# mainboard.net
KiCad netlist of a schematic drawn in EAGLE
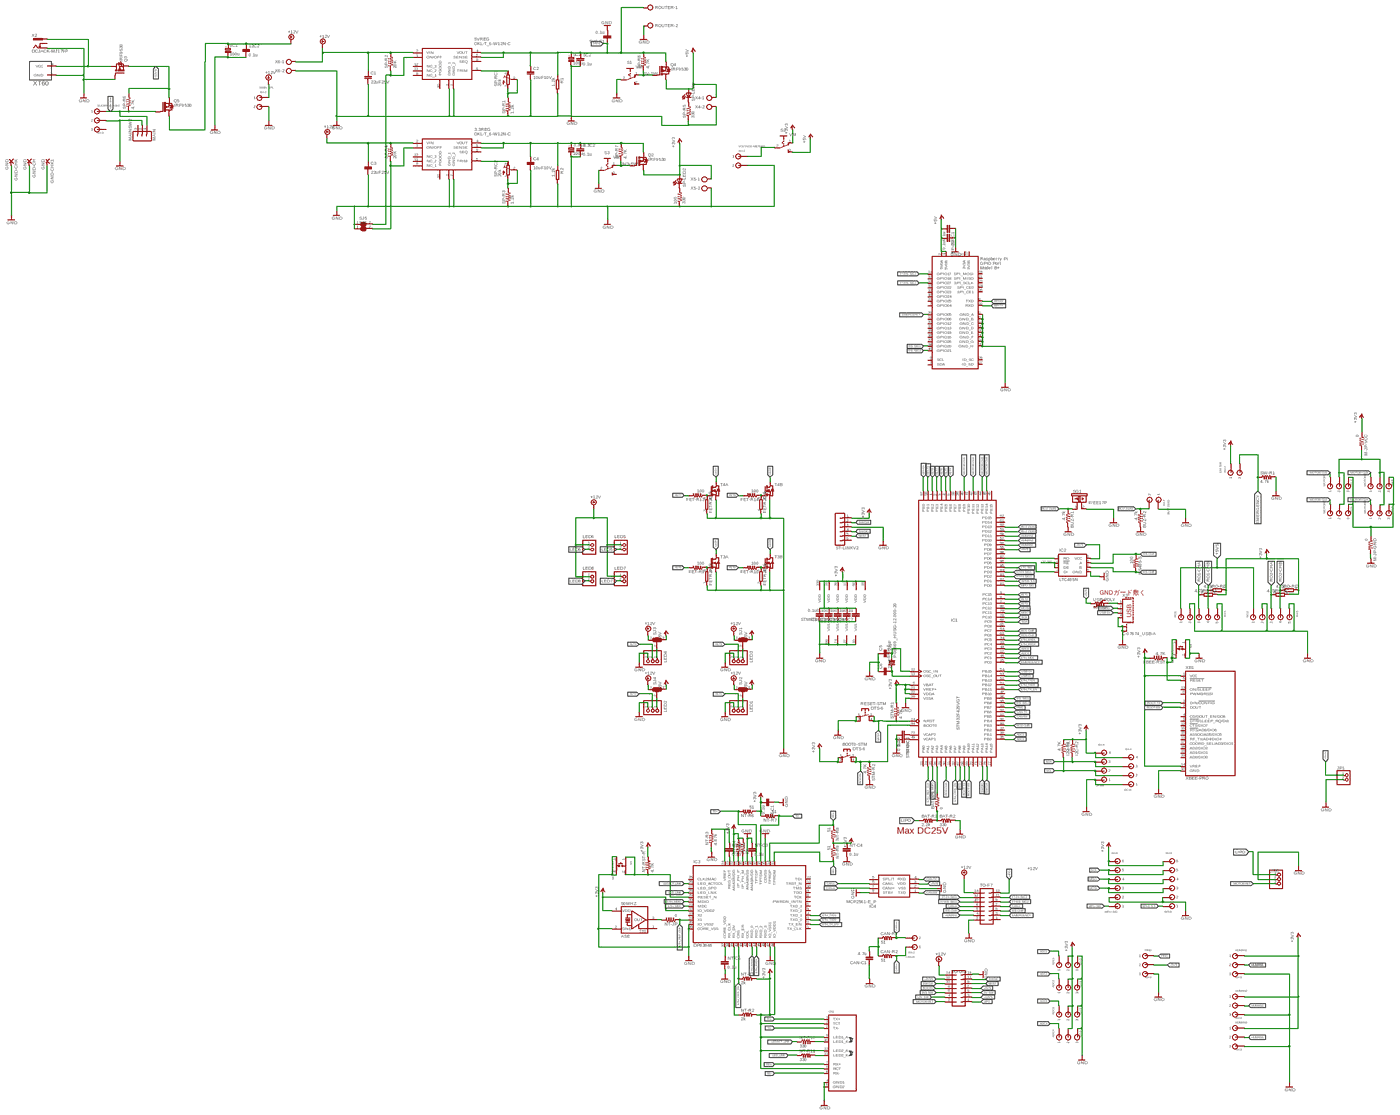
[diagram p0: schematic, sheet 1, overview]
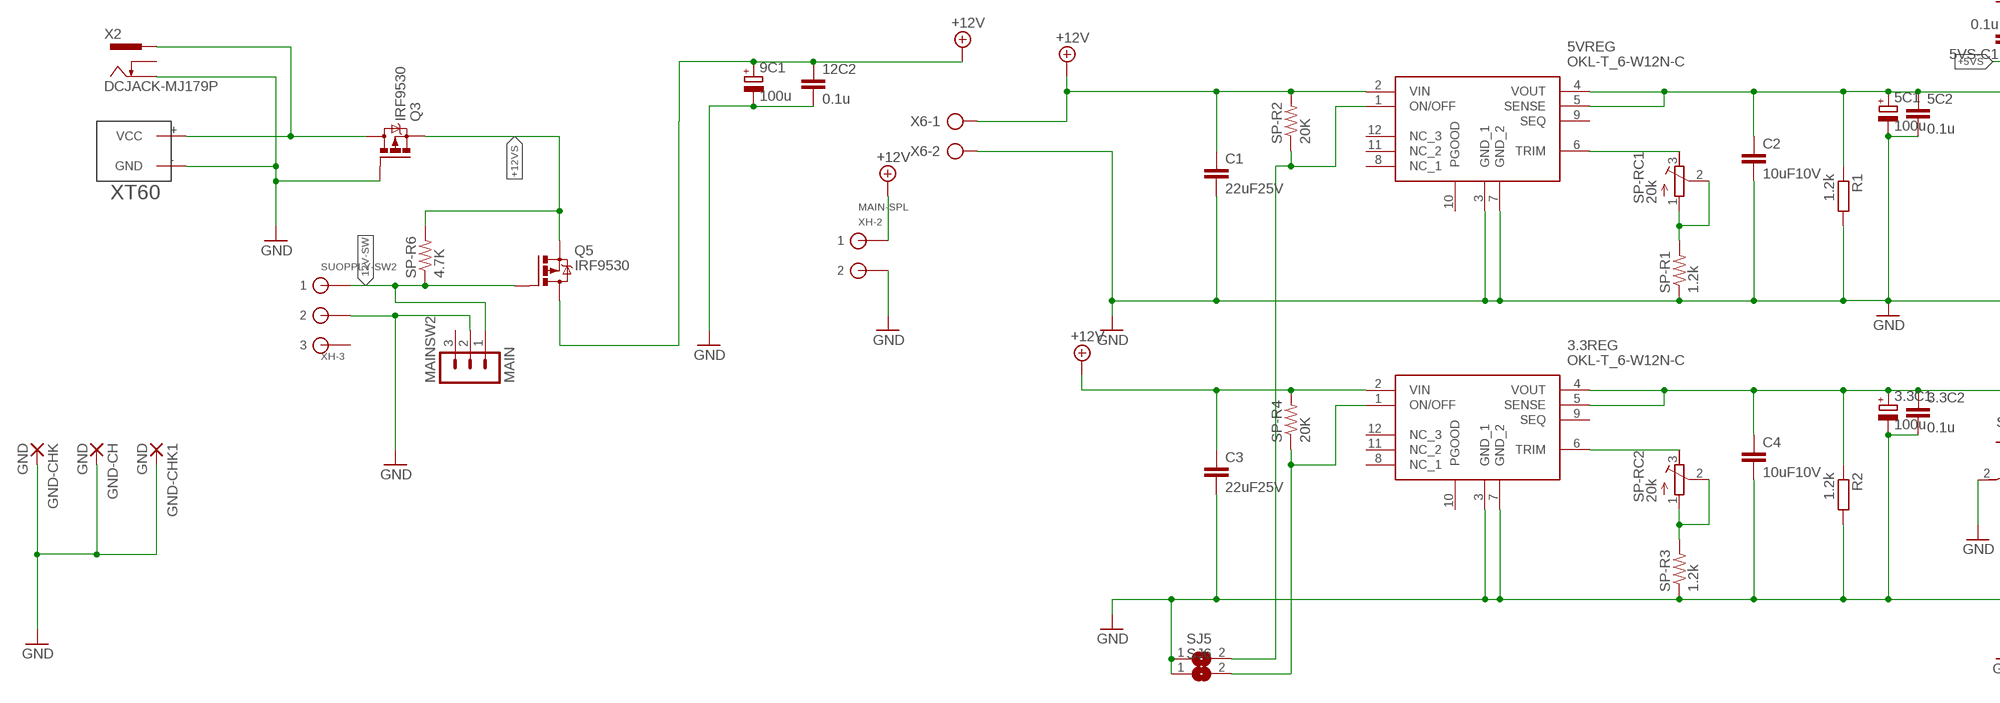
[diagram p1: schematic, sheet 1, part 1 of 4]
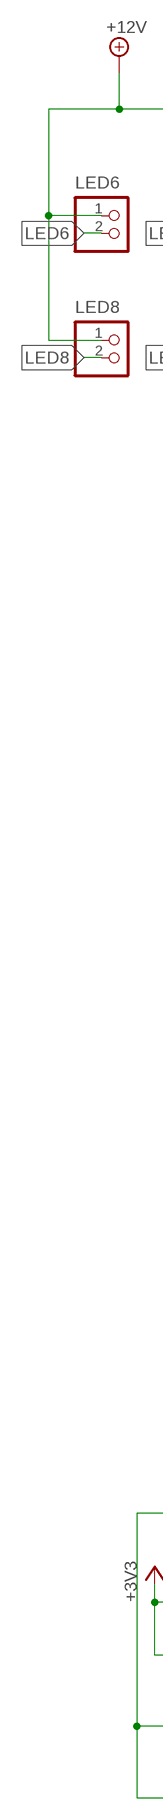
[diagram p2: schematic, sheet 1, part 2 of 4]
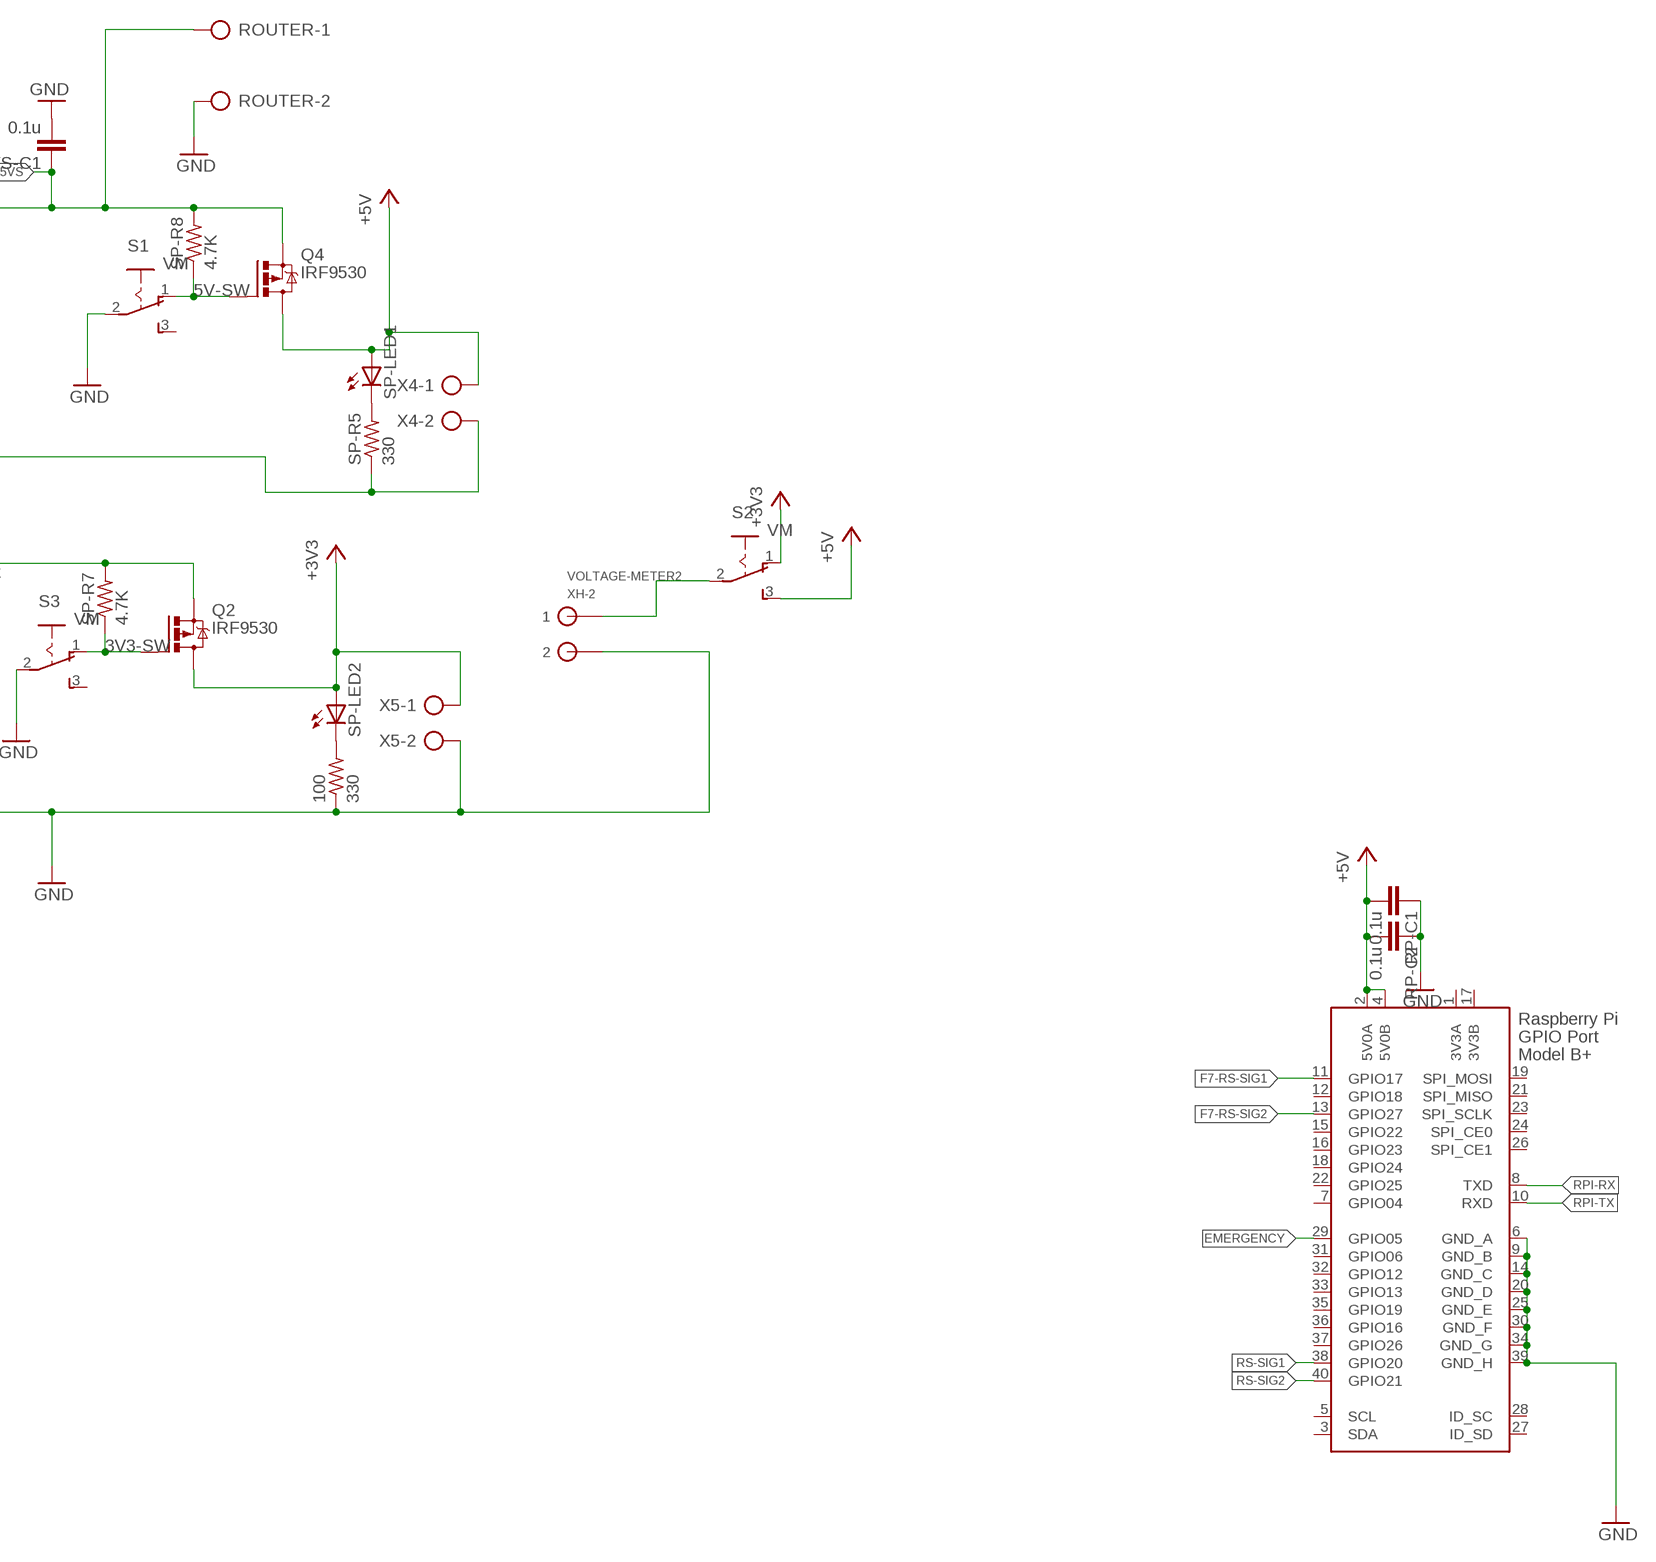
[diagram p3: schematic, sheet 1, part 3 of 4]
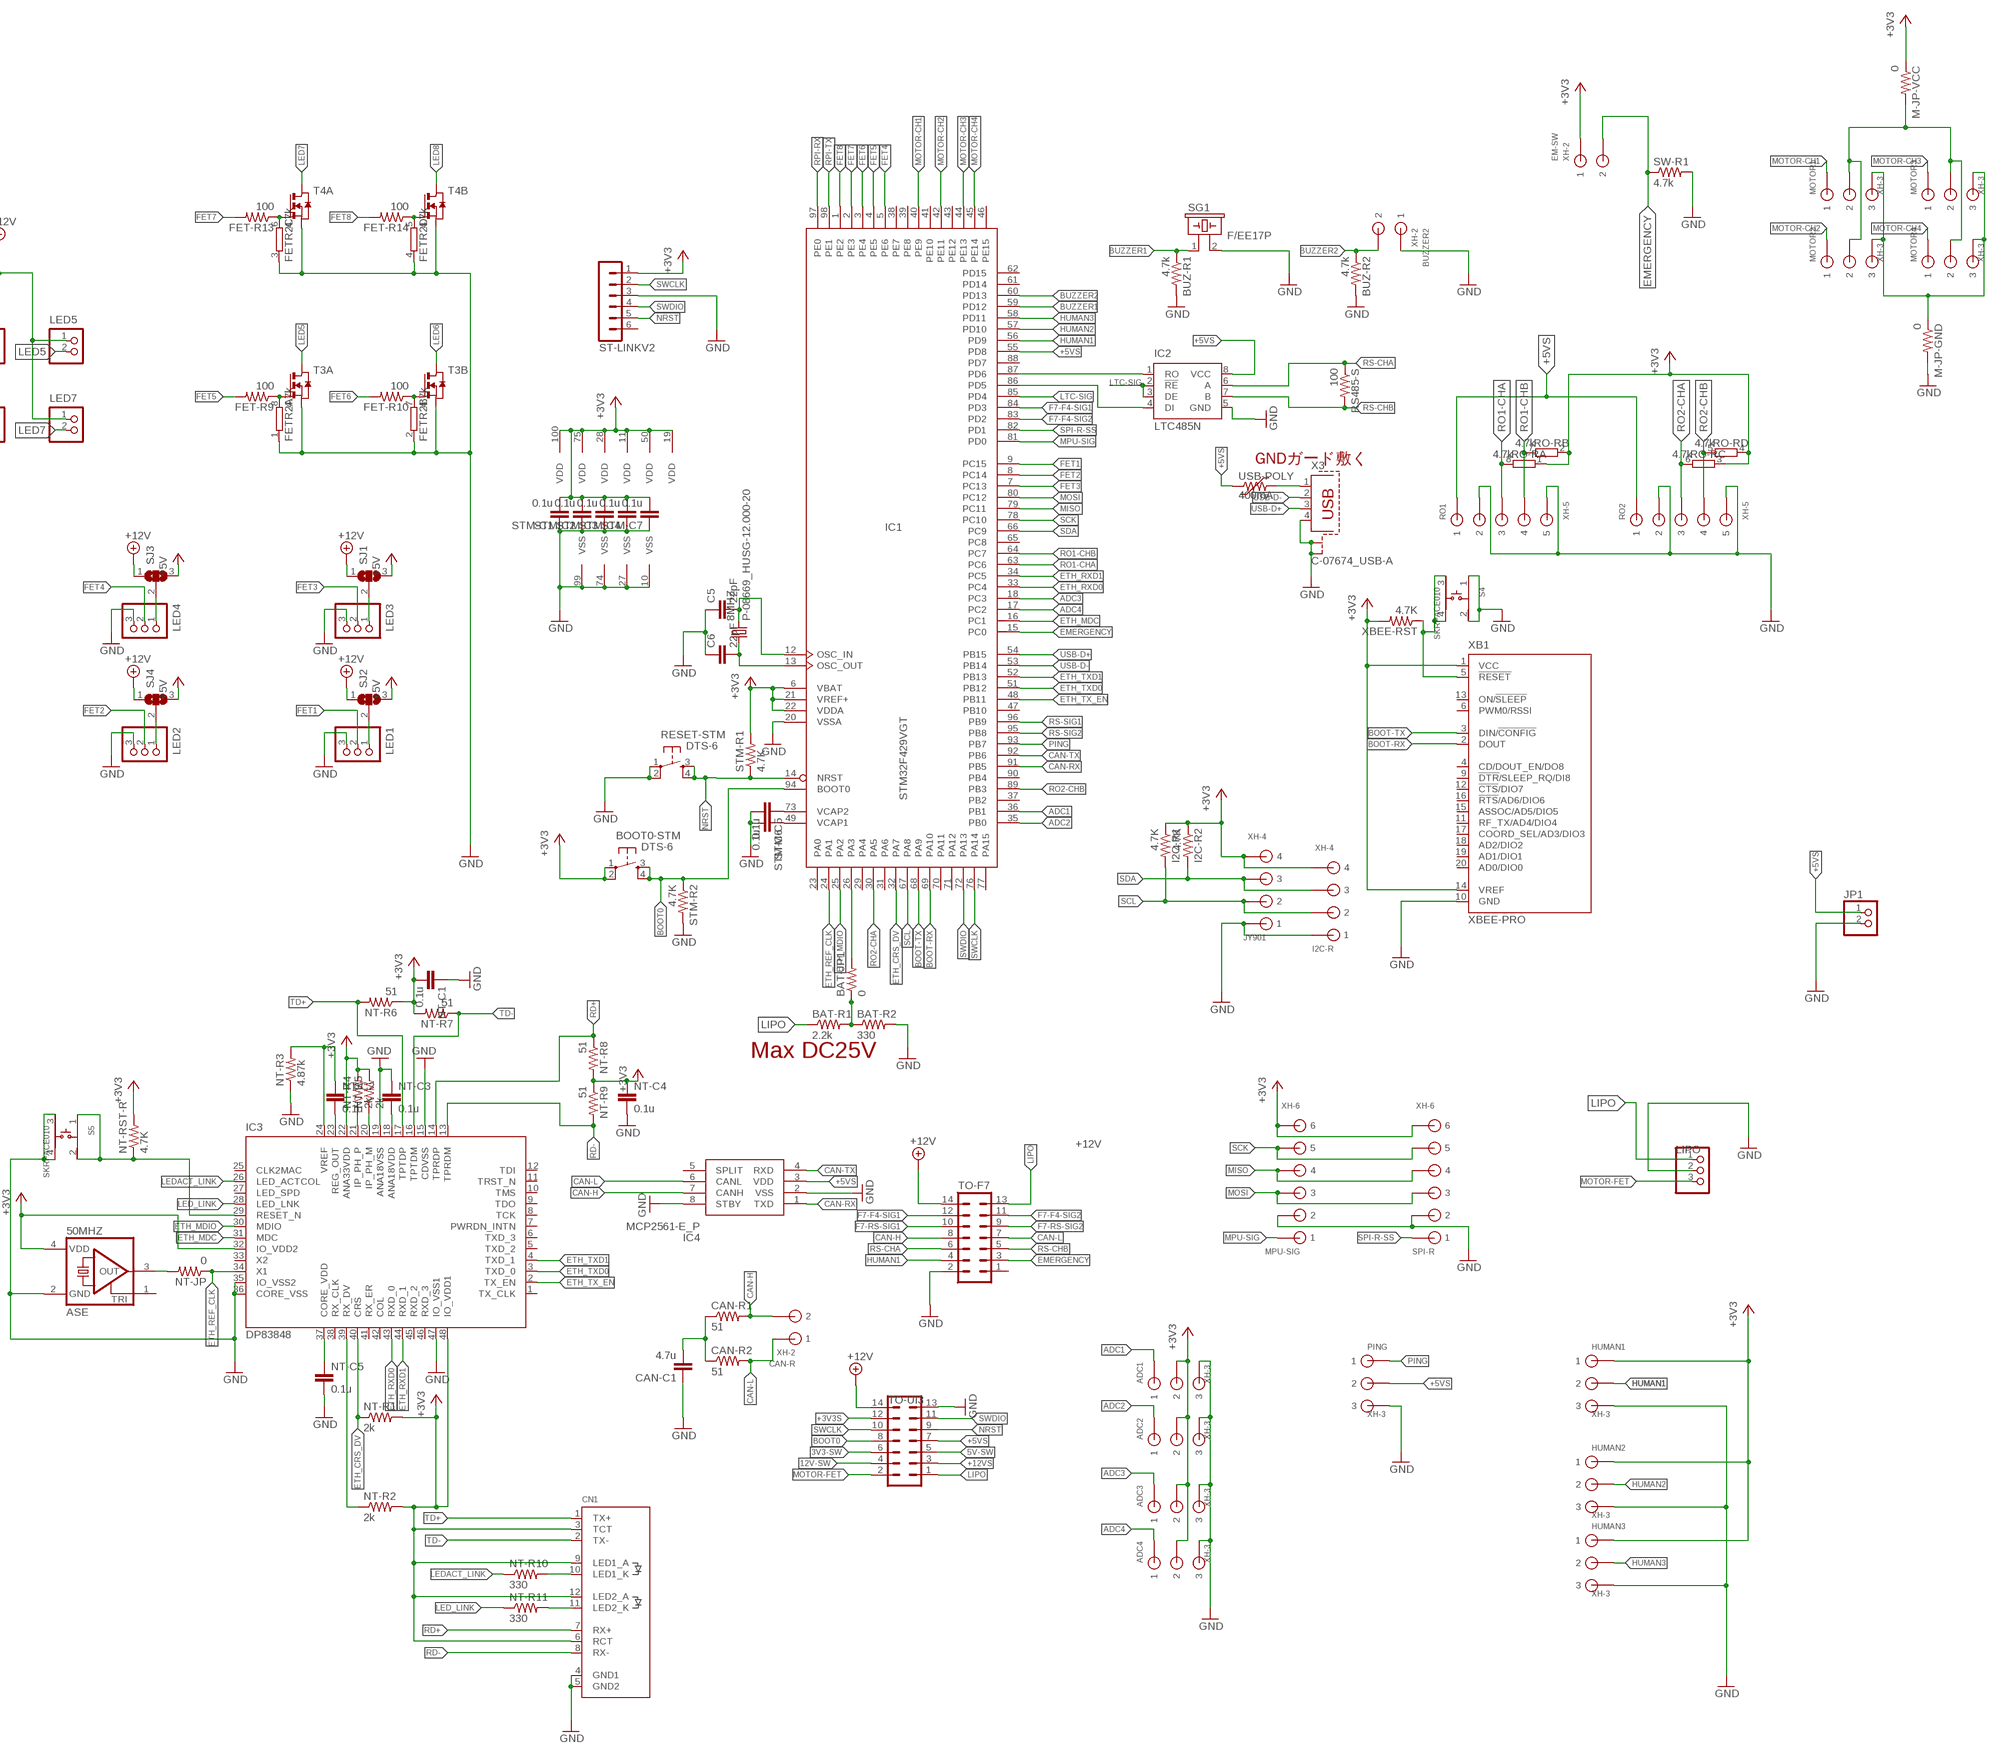
[diagram p4: schematic, sheet 1, part 4 of 4]

(export (version "E")
  (design (tool "Eeschema 10.0.6"))
  (components
    (comp (ref "3.3C1")
      (value "100u")
      (footprint "eagle-import:D_7343-31R")
      (fields (field (name "SPICEPREFIX") "B"))
      (libsource (lib "eagle-import") (part "CPOL-EUD/7343-31R"))
    )
    (comp (ref "3.3C2")
      (value "0.1u")
      (footprint "eagle-import:C0805")
      (fields (field (name "SPICEPREFIX") "B"))
      (libsource (lib "eagle-import") (part "C-EUC0805"))
    )
    (comp (ref "3.3REG")
      (value "OKL-T_6-W12N-C")
      (footprint "eagle-import:OKL-T_3-W5")
      (fields (field (name "ARROW_PART_NUMBER") "OKL-T/6-W12N-C") (field (name "RS_PART_NUMBER") "1736944P"))
      (libsource (lib "eagle-import") (part "OKL-T_6-W12N-C"))
    )
    (comp (ref "5C1")
      (value "100u")
      (footprint "eagle-import:D_7343-31R")
      (fields (field (name "SPICEPREFIX") "B"))
      (libsource (lib "eagle-import") (part "CPOL-EUD/7343-31R"))
    )
    (comp (ref "5C2")
      (value "0.1u")
      (footprint "eagle-import:C0805")
      (fields (field (name "SPICEPREFIX") "B"))
      (libsource (lib "eagle-import") (part "C-EUC0805"))
    )
    (comp (ref "5VREG")
      (value "OKL-T_6-W12N-C")
      (footprint "eagle-import:OKL-T_3-W5")
      (fields (field (name "ARROW_PART_NUMBER") "OKL-T/6-W12N-C") (field (name "RS_PART_NUMBER") "1736944P"))
      (libsource (lib "eagle-import") (part "OKL-T_6-W12N-C"))
    )
    (comp (ref "5VS-C1")
      (value "0.1u")
      (footprint "eagle-import:C0805")
      (libsource (lib "eagle-import") (part "C-EUC0805"))
    )
    (comp (ref "8MHZ")
      (value "P-08669_HUSG-12.000-20")
      (footprint "eagle-import:HC49U-V")
      (libsource (lib "eagle-import") (part "P-08669_HUSG-12.000-20"))
    )
    (comp (ref "9C1")
      (value "100u")
      (footprint "eagle-import:D_7343-31R")
      (fields (field (name "SPICEPREFIX") "B"))
      (libsource (lib "eagle-import") (part "CPOL-EUD/7343-31R"))
    )
    (comp (ref "12C2")
      (value "0.1u")
      (footprint "eagle-import:C0805")
      (fields (field (name "SPICEPREFIX") "B"))
      (libsource (lib "eagle-import") (part "C-EUC0805"))
    )
    (comp (ref "50MHZ")
      (value "ASE")
      (footprint "eagle-import:ASE")
      (libsource (lib "eagle-import") (part "ASE"))
    )
    (comp (ref "100")
      (value "330")
      (footprint "eagle-import:R0805")
      (libsource (lib "eagle-import") (part "R-US_R0805"))
    )
    (comp (ref "ADC1")
      (value "XH-3")
      (footprint "eagle-import:CON3")
      (libsource (lib "eagle-import") (part "XH-3"))
    )
    (comp (ref "ADC2")
      (value "XH-3")
      (footprint "eagle-import:CON3")
      (libsource (lib "eagle-import") (part "XH-3"))
    )
    (comp (ref "ADC3")
      (value "XH-3")
      (footprint "eagle-import:CON3")
      (libsource (lib "eagle-import") (part "XH-3"))
    )
    (comp (ref "ADC4")
      (value "XH-3")
      (footprint "eagle-import:CON3")
      (libsource (lib "eagle-import") (part "XH-3"))
    )
    (comp (ref "BAT-JP1")
      (value "0")
      (footprint "eagle-import:R0805")
      (libsource (lib "eagle-import") (part "R-US_R0805"))
    )
    (comp (ref "BAT-R1")
      (value "2.2k")
      (footprint "eagle-import:R0805")
      (libsource (lib "eagle-import") (part "R-US_R0805"))
    )
    (comp (ref "BAT-R2")
      (value "330")
      (footprint "eagle-import:R0805")
      (libsource (lib "eagle-import") (part "R-US_R0805"))
    )
    (comp (ref "BOOT0-STM")
      (value "DTS-6")
      (footprint "eagle-import:DTS-6")
      (libsource (lib "eagle-import") (part "DTS-6"))
    )
    (comp (ref "BUZ-R1")
      (value "4.7k")
      (footprint "eagle-import:R0805")
      (libsource (lib "eagle-import") (part "R-US_R0805"))
    )
    (comp (ref "BUZ-R2")
      (value "4.7k")
      (footprint "eagle-import:R0805")
      (libsource (lib "eagle-import") (part "R-US_R0805"))
    )
    (comp (ref "BUZZER2")
      (value "XH-2")
      (footprint "eagle-import:CON2")
      (libsource (lib "eagle-import") (part "XH-2"))
    )
    (comp (ref "C1")
      (value "22uF25V")
      (footprint "eagle-import:C2012")
      (libsource (lib "eagle-import") (part "resistor_348_C-EUC2012"))
    )
    (comp (ref "C2")
      (value "10uF10V")
      (footprint "eagle-import:C2012")
      (libsource (lib "eagle-import") (part "resistor_348_C-EUC2012"))
    )
    (comp (ref "C3")
      (value "22uF25V")
      (footprint "eagle-import:C2012")
      (libsource (lib "eagle-import") (part "resistor_348_C-EUC2012"))
    )
    (comp (ref "C4")
      (value "10uF10V")
      (footprint "eagle-import:C2012")
      (libsource (lib "eagle-import") (part "resistor_348_C-EUC2012"))
    )
    (comp (ref "C5")
      (value "22pF")
      (footprint "eagle-import:C1608")
      (libsource (lib "eagle-import") (part "resistor_348_C-EUC1608"))
    )
    (comp (ref "C6")
      (value "22pF")
      (footprint "eagle-import:C1608")
      (libsource (lib "eagle-import") (part "resistor_348_C-EUC1608"))
    )
    (comp (ref "CAN-C1")
      (value "4.7u")
      (footprint "eagle-import:C0805")
      (libsource (lib "eagle-import") (part "C-EUC0805"))
    )
    (comp (ref "CAN-R")
      (value "XH-2")
      (footprint "eagle-import:CON2")
      (libsource (lib "eagle-import") (part "XH-2"))
    )
    (comp (ref "CAN-R1")
      (value "51")
      (footprint "eagle-import:R0805")
      (libsource (lib "eagle-import") (part "R-US_R0805"))
    )
    (comp (ref "CAN-R2")
      (value "51")
      (footprint "eagle-import:R0805")
      (libsource (lib "eagle-import") (part "R-US_R0805"))
    )
    (comp (ref "CN1")
      (value "P-04809_RJLD260TC1")
      (footprint "eagle-import:RJ45_PULSEJACK")
      (libsource (lib "eagle-import") (part "P-04809_RJLD260TC1"))
    )
    (comp (ref "EM-SW")
      (value "XH-2")
      (footprint "eagle-import:CON2")
      (libsource (lib "eagle-import") (part "XH-2"))
    )
    (comp (ref "FET-R9")
      (value "100")
      (footprint "eagle-import:R0805")
      (libsource (lib "eagle-import") (part "R-US_R0805"))
    )
    (comp (ref "FET-R10")
      (value "100")
      (footprint "eagle-import:R0805")
      (libsource (lib "eagle-import") (part "R-US_R0805"))
    )
    (comp (ref "FET-R13")
      (value "100")
      (footprint "eagle-import:R0805")
      (libsource (lib "eagle-import") (part "R-US_R0805"))
    )
    (comp (ref "FET-R14")
      (value "100")
      (footprint "eagle-import:R0805")
      (libsource (lib "eagle-import") (part "R-US_R0805"))
    )
    (comp (ref "FETR2")
      (value "4.7k")
      (footprint "eagle-import:EXBN8V")
      (libsource (lib "eagle-import") (part "4R-NEXBN8V"))
    )
    (comp (ref "GND-CH")
      (value "GND")
      (footprint "eagle-import:SMD2,54-5,08")
      (libsource (lib "eagle-import") (part "SMD5"))
    )
    (comp (ref "GND-CHK")
      (value "GND")
      (footprint "eagle-import:2,15_1,0")
      (libsource (lib "eagle-import") (part "2,15/1,0"))
    )
    (comp (ref "GND-CHK1")
      (value "GND")
      (footprint "eagle-import:2,15_1,0")
      (libsource (lib "eagle-import") (part "2,15/1,0"))
    )
    (comp (ref "HUMAN1")
      (value "XH-3")
      (footprint "eagle-import:CON3")
      (libsource (lib "eagle-import") (part "XH-3"))
    )
    (comp (ref "HUMAN2")
      (value "XH-3")
      (footprint "eagle-import:CON3")
      (libsource (lib "eagle-import") (part "XH-3"))
    )
    (comp (ref "HUMAN3")
      (value "XH-3")
      (footprint "eagle-import:CON3")
      (libsource (lib "eagle-import") (part "XH-3"))
    )
    (comp (ref "I2C-R")
      (value "XH-4")
      (footprint "eagle-import:CON4")
      (libsource (lib "eagle-import") (part "XH-4"))
    )
    (comp (ref "I2C-R1")
      (value "4.7K")
      (footprint "eagle-import:R0805")
      (libsource (lib "eagle-import") (part "R-US_R0805"))
    )
    (comp (ref "I2C-R2")
      (value "4.7K")
      (footprint "eagle-import:R0805")
      (libsource (lib "eagle-import") (part "R-US_R0805"))
    )
    (comp (ref "IC1")
      (value "STM32F429VGT")
      (footprint "eagle-import:LQFP100")
      (libsource (lib "eagle-import") (part "STM32F429VTG"))
    )
    (comp (ref "IC2")
      (value "LTC485N")
      (footprint "eagle-import:DIL08")
      (libsource (lib "eagle-import") (part "LTC485N"))
    )
    (comp (ref "IC3")
      (value "DP83848")
      (footprint "eagle-import:LQFP48")
      (fields (field (name "MPN") "DP83848VYB"))
      (libsource (lib "eagle-import") (part "DP83848"))
    )
    (comp (ref "IC4")
      (value "MCP2561-E_P")
      (footprint "eagle-import:DIP781W56P254L950H533Q8N")
      (fields
        (field (name "MANUFACTURER_PART_NUMBER") "MCP2561-E/P")
        (field (name "MOUSER_PART_NUMBER") "579-MCP2561-E/P")
        (field (name "RS_PART_NUMBER") "1652124")
      )
      (libsource (lib "eagle-import") (part "MCP2561-E_P"))
    )
    (comp (ref "JP1")
      (value "PINHD-1X2/90")
      (footprint "eagle-import:1X02_90")
      (libsource (lib "eagle-import") (part "PINHD-1X2/90"))
    )
    (comp (ref "JY901")
      (value "XH-4")
      (footprint "eagle-import:CON4")
      (libsource (lib "eagle-import") (part "XH-4"))
    )
    (comp (ref "LED1")
      (value "B3P-VH")
      (footprint "eagle-import:B3P-VH")
      (libsource (lib "eagle-import") (part "B3P-VH"))
    )
    (comp (ref "LED2")
      (value "B3P-VH")
      (footprint "eagle-import:B3P-VH")
      (libsource (lib "eagle-import") (part "B3P-VH"))
    )
    (comp (ref "LED3")
      (value "B3P-VH")
      (footprint "eagle-import:B3P-VH")
      (libsource (lib "eagle-import") (part "B3P-VH"))
    )
    (comp (ref "LED4")
      (value "B3P-VH")
      (footprint "eagle-import:B3P-VH")
      (libsource (lib "eagle-import") (part "B3P-VH"))
    )
    (comp (ref "LED5")
      (value "B2P-VH")
      (footprint "eagle-import:B2P-VH")
      (libsource (lib "eagle-import") (part "B2P-VH"))
    )
    (comp (ref "LED6")
      (value "B2P-VH")
      (footprint "eagle-import:B2P-VH")
      (libsource (lib "eagle-import") (part "B2P-VH"))
    )
    (comp (ref "LED7")
      (value "B2P-VH")
      (footprint "eagle-import:B2P-VH")
      (libsource (lib "eagle-import") (part "B2P-VH"))
    )
    (comp (ref "LED8")
      (value "B2P-VH")
      (footprint "eagle-import:B2P-VH")
      (libsource (lib "eagle-import") (part "B2P-VH"))
    )
    (comp (ref "LIPO")
      (value "B3P-VH")
      (footprint "eagle-import:B3P-VH")
      (libsource (lib "eagle-import") (part "B3P-VH"))
    )
    (comp (ref "M-JP-GND")
      (value "0")
      (footprint "eagle-import:R0805")
      (libsource (lib "eagle-import") (part "R-US_R0805"))
    )
    (comp (ref "M-JP-VCC")
      (value "0")
      (footprint "eagle-import:R0805")
      (libsource (lib "eagle-import") (part "R-US_R0805"))
    )
    (comp (ref "MAIN-SPL")
      (value "XH-2")
      (footprint "eagle-import:CON2")
      (libsource (lib "eagle-import") (part "forprint_XH-2"))
    )
    (comp (ref "MAINSW2")
      (value "MAIN")
      (footprint "eagle-import:MA03-1")
      (libsource (lib "eagle-import") (part "MA03-1"))
    )
    (comp (ref "MOTOR1")
      (value "XH-3")
      (footprint "eagle-import:CON3")
      (libsource (lib "eagle-import") (part "XH-3"))
    )
    (comp (ref "MOTOR2")
      (value "XH-3")
      (footprint "eagle-import:CON3")
      (libsource (lib "eagle-import") (part "XH-3"))
    )
    (comp (ref "MOTOR3")
      (value "XH-3")
      (footprint "eagle-import:CON3")
      (libsource (lib "eagle-import") (part "XH-3"))
    )
    (comp (ref "MOTOR4")
      (value "XH-3")
      (footprint "eagle-import:CON3")
      (libsource (lib "eagle-import") (part "XH-3"))
    )
    (comp (ref "MPU-SIG")
      (value "XH-6")
      (footprint "eagle-import:CON6")
      (libsource (lib "eagle-import") (part "XH-6"))
    )
    (comp (ref "NT-C1")
      (value "0.1u")
      (footprint "eagle-import:C0805")
      (libsource (lib "eagle-import") (part "C-EUC0805"))
    )
    (comp (ref "NT-C2")
      (value "0.1u")
      (footprint "eagle-import:C0805")
      (libsource (lib "eagle-import") (part "C-EUC0805"))
    )
    (comp (ref "NT-C3")
      (value "0.1u")
      (footprint "eagle-import:C0805")
      (libsource (lib "eagle-import") (part "C-EUC0805"))
    )
    (comp (ref "NT-C4")
      (value "0.1u")
      (footprint "eagle-import:C0805")
      (libsource (lib "eagle-import") (part "C-EUC0805"))
    )
    (comp (ref "NT-C5")
      (value "0.1u")
      (footprint "eagle-import:C0805")
      (libsource (lib "eagle-import") (part "C-EUC0805"))
    )
    (comp (ref "NT-JP")
      (value "0")
      (footprint "eagle-import:R0805")
      (libsource (lib "eagle-import") (part "R-US_R0805"))
    )
    (comp (ref "NT-R1")
      (value "2k")
      (footprint "eagle-import:R0805")
      (libsource (lib "eagle-import") (part "R-US_R0805"))
    )
    (comp (ref "NT-R2")
      (value "2k")
      (footprint "eagle-import:R0805")
      (libsource (lib "eagle-import") (part "R-US_R0805"))
    )
    (comp (ref "NT-R3")
      (value "4.87k")
      (footprint "eagle-import:R0805")
      (libsource (lib "eagle-import") (part "R-US_R0805"))
    )
    (comp (ref "NT-R4")
      (value "2k")
      (footprint "eagle-import:R0805")
      (libsource (lib "eagle-import") (part "R-US_R0805"))
    )
    (comp (ref "NT-R5")
      (value "2k")
      (footprint "eagle-import:R0805")
      (libsource (lib "eagle-import") (part "R-US_R0805"))
    )
    (comp (ref "NT-R6")
      (value "51")
      (footprint "eagle-import:R0805")
      (libsource (lib "eagle-import") (part "resistor_348_R-US_R0805"))
    )
    (comp (ref "NT-R7")
      (value "51")
      (footprint "eagle-import:R0805")
      (libsource (lib "eagle-import") (part "resistor_348_R-US_R0805"))
    )
    (comp (ref "NT-R8")
      (value "51")
      (footprint "eagle-import:R0805")
      (libsource (lib "eagle-import") (part "resistor_348_R-US_R0805"))
    )
    (comp (ref "NT-R9")
      (value "51")
      (footprint "eagle-import:R0805")
      (libsource (lib "eagle-import") (part "resistor_348_R-US_R0805"))
    )
    (comp (ref "NT-R10")
      (value "330")
      (footprint "eagle-import:R0805")
      (libsource (lib "eagle-import") (part "R-US_R0805"))
    )
    (comp (ref "NT-R11")
      (value "330")
      (footprint "eagle-import:R0805")
      (libsource (lib "eagle-import") (part "R-US_R0805"))
    )
    (comp (ref "NT-RST-R")
      (value "4.7K")
      (footprint "eagle-import:R0805")
      (libsource (lib "eagle-import") (part "R-US_R0805"))
    )
    (comp (ref "PING")
      (value "XH-3")
      (footprint "eagle-import:CON3")
      (libsource (lib "eagle-import") (part "XH-3"))
    )
    (comp (ref "Q2")
      (value "IRF9530")
      (footprint "eagle-import:TO220BV")
      (libsource (lib "eagle-import") (part "IRF9530"))
    )
    (comp (ref "Q3")
      (value "IRF9530")
      (footprint "eagle-import:TO220BV")
      (libsource (lib "eagle-import") (part "IRF9530"))
    )
    (comp (ref "Q4")
      (value "IRF9530")
      (footprint "eagle-import:TO220BV")
      (libsource (lib "eagle-import") (part "IRF9530"))
    )
    (comp (ref "Q5")
      (value "IRF9530")
      (footprint "eagle-import:TO220BV")
      (libsource (lib "eagle-import") (part "IRF9530"))
    )
    (comp (ref "R1")
      (value "1.2k")
      (footprint "eagle-import:0204_7")
      (libsource (lib "eagle-import") (part "R-EU_0204/7"))
    )
    (comp (ref "R2")
      (value "1.2k")
      (footprint "eagle-import:0204_7")
      (libsource (lib "eagle-import") (part "R-EU_0204/7"))
    )
    (comp (ref "RESET-STM")
      (value "DTS-6")
      (footprint "eagle-import:DTS-6")
      (libsource (lib "eagle-import") (part "DTS-6"))
    )
    (comp (ref "RO-R")
      (value "4.7k")
      (footprint "eagle-import:EXBN8V")
      (libsource (lib "eagle-import") (part "4R-NEXBN8V"))
    )
    (comp (ref "RO1")
      (value "XH-5")
      (footprint "eagle-import:CON5")
      (libsource (lib "eagle-import") (part "XH-5"))
    )
    (comp (ref "RO2")
      (value "XH-5")
      (footprint "eagle-import:CON5")
      (libsource (lib "eagle-import") (part "XH-5"))
    )
    (comp (ref "ROUTER")
      (value "AK500/2-H")
      (footprint "eagle-import:AK500_2-H")
      (libsource (lib "eagle-import") (part "AK500/2-H"))
    )
    (comp (ref "RP-C1")
      (value "0.1u")
      (footprint "eagle-import:C0805")
      (libsource (lib "eagle-import") (part "C-EUC0805"))
    )
    (comp (ref "RP-C2")
      (value "0.1u")
      (footprint "eagle-import:C0805")
      (libsource (lib "eagle-import") (part "C-EUC0805"))
    )
    (comp (ref "RS485-S")
      (value "100")
      (footprint "eagle-import:R0805")
      (libsource (lib "eagle-import") (part "R-US_R0805"))
    )
    (comp (ref "S1")
      (value "VM")
      (footprint "eagle-import:M251")
      (libsource (lib "eagle-import") (part "M251"))
    )
    (comp (ref "S2")
      (value "VM")
      (footprint "eagle-import:M251")
      (libsource (lib "eagle-import") (part "M251"))
    )
    (comp (ref "S3")
      (value "VM")
      (footprint "eagle-import:M251")
      (libsource (lib "eagle-import") (part "M251"))
    )
    (comp (ref "S4")
      (value "SKRPACE010")
      (footprint "eagle-import:SW_SKRPACE010")
      (fields (field (name "MF") "ALPS"))
      (libsource (lib "eagle-import") (part "SKRPACE010"))
    )
    (comp (ref "S5")
      (value "SKRPACE010")
      (footprint "eagle-import:SW_SKRPACE010")
      (fields (field (name "MF") "ALPS"))
      (libsource (lib "eagle-import") (part "SKRPACE010"))
    )
    (comp (ref "SG1")
      (value "F/EE17P")
      (footprint "eagle-import:F_EE17P")
      (libsource (lib "eagle-import") (part "F/EE17P"))
    )
    (comp (ref "SJ1")
      (value "SJ2WW")
      (footprint "eagle-import:SJ_2W")
      (libsource (lib "eagle-import") (part "SJ2WW"))
    )
    (comp (ref "SJ2")
      (value "SJ2WW")
      (footprint "eagle-import:SJ_2W")
      (libsource (lib "eagle-import") (part "SJ2WW"))
    )
    (comp (ref "SJ3")
      (value "SJ2WW")
      (footprint "eagle-import:SJ_2W")
      (libsource (lib "eagle-import") (part "SJ2WW"))
    )
    (comp (ref "SJ4")
      (value "SJ2WW")
      (footprint "eagle-import:SJ_2W")
      (libsource (lib "eagle-import") (part "SJ2WW"))
    )
    (comp (ref "SJ5") (value "SJ") (footprint "eagle-import:SJ") (libsource (lib "eagle-import") (part "SJ")))
    (comp (ref "SJ6") (value "SJ") (footprint "eagle-import:SJ") (libsource (lib "eagle-import") (part "SJ")))
    (comp (ref "SP-LED1")
      (value "LEDCHIPLED_0805")
      (footprint "eagle-import:CHIPLED_0805")
      (libsource (lib "eagle-import") (part "LEDCHIPLED_0805"))
    )
    (comp (ref "SP-LED2")
      (value "LEDCHIPLED_0805")
      (footprint "eagle-import:CHIPLED_0805")
      (libsource (lib "eagle-import") (part "LEDCHIPLED_0805"))
    )
    (comp (ref "SP-R1")
      (value "1.2k")
      (footprint "eagle-import:R0805")
      (libsource (lib "eagle-import") (part "R-US_R0805"))
    )
    (comp (ref "SP-R2")
      (value "20K")
      (footprint "eagle-import:R0805")
      (libsource (lib "eagle-import") (part "R-US_R0805"))
    )
    (comp (ref "SP-R3")
      (value "1.2k")
      (footprint "eagle-import:R0805")
      (libsource (lib "eagle-import") (part "R-US_R0805"))
    )
    (comp (ref "SP-R4")
      (value "20K")
      (footprint "eagle-import:R0805")
      (libsource (lib "eagle-import") (part "R-US_R0805"))
    )
    (comp (ref "SP-R5")
      (value "330")
      (footprint "eagle-import:R0805")
      (libsource (lib "eagle-import") (part "R-US_R0805"))
    )
    (comp (ref "SP-R6")
      (value "4.7K")
      (footprint "eagle-import:R0805")
      (libsource (lib "eagle-import") (part "R-US_R0805"))
    )
    (comp (ref "SP-R7")
      (value "4.7K")
      (footprint "eagle-import:R0805")
      (libsource (lib "eagle-import") (part "R-US_R0805"))
    )
    (comp (ref "SP-R8")
      (value "4.7K")
      (footprint "eagle-import:R0805")
      (libsource (lib "eagle-import") (part "R-US_R0805"))
    )
    (comp (ref "SP-RC1")
      (value "20k")
      (footprint "eagle-import:RTRIM3296W")
      (libsource (lib "eagle-import") (part "R-TRIMM3296W"))
    )
    (comp (ref "SP-RC2")
      (value "20k")
      (footprint "eagle-import:RTRIM3296W")
      (libsource (lib "eagle-import") (part "R-TRIMM3296W"))
    )
    (comp (ref "SPI-R")
      (value "XH-6")
      (footprint "eagle-import:CON6")
      (libsource (lib "eagle-import") (part "XH-6"))
    )
    (comp (ref "ST-LINKV2")
      (value "MA06-1")
      (footprint "eagle-import:MA06-1")
      (libsource (lib "eagle-import") (part "MA06-1"))
    )
    (comp (ref "STM-C1")
      (value "0.1u")
      (footprint "eagle-import:C0805")
      (libsource (lib "eagle-import") (part "C-EUC0805"))
    )
    (comp (ref "STM-C2")
      (value "0.1u")
      (footprint "eagle-import:C0805")
      (libsource (lib "eagle-import") (part "C-EUC0805"))
    )
    (comp (ref "STM-C3")
      (value "0.1u")
      (footprint "eagle-import:C0805")
      (libsource (lib "eagle-import") (part "C-EUC0805"))
    )
    (comp (ref "STM-C4")
      (value "0.1u")
      (footprint "eagle-import:C0805")
      (libsource (lib "eagle-import") (part "C-EUC0805"))
    )
    (comp (ref "STM-C5")
      (value "0.1u")
      (footprint "eagle-import:C0805")
      (libsource (lib "eagle-import") (part "C-EUC0805"))
    )
    (comp (ref "STM-C6")
      (value "0.1u")
      (footprint "eagle-import:C0805")
      (libsource (lib "eagle-import") (part "C-EUC0805"))
    )
    (comp (ref "STM-C7")
      (value "0.1u")
      (footprint "eagle-import:C0805")
      (libsource (lib "eagle-import") (part "C-EUC0805"))
    )
    (comp (ref "STM-R1")
      (value "4.7K")
      (footprint "eagle-import:R0805")
      (libsource (lib "eagle-import") (part "R-US_R0805"))
    )
    (comp (ref "STM-R2")
      (value "4.7K")
      (footprint "eagle-import:R0805")
      (libsource (lib "eagle-import") (part "R-US_R0805"))
    )
    (comp (ref "SUOPPLY-SW2")
      (value "XH-3")
      (footprint "eagle-import:CON3")
      (libsource (lib "eagle-import") (part "forprint_XH-3"))
    )
    (comp (ref "SW-R1")
      (value "4.7k")
      (footprint "eagle-import:R0805")
      (libsource (lib "eagle-import") (part "R-US_R0805"))
    )
    (comp (ref "T3")
      (value "NMOS2SO8")
      (footprint "eagle-import:SO8")
      (libsource (lib "eagle-import") (part "NMOS2SO8"))
    )
    (comp (ref "T4")
      (value "NMOS2SO8")
      (footprint "eagle-import:SO8")
      (libsource (lib "eagle-import") (part "NMOS2SO8"))
    )
    (comp (ref "TO-F7")
      (value "ML14")
      (footprint "eagle-import:ML14")
      (libsource (lib "eagle-import") (part "ML14"))
    )
    (comp (ref "TO-UI3")
      (value "ML14")
      (footprint "eagle-import:ML14")
      (libsource (lib "eagle-import") (part "ML14"))
    )
    (comp (ref "U$2")
      (value "XT60")
      (footprint "eagle-import:XT60")
      (libsource (lib "eagle-import") (part "XT60"))
    )
    (comp (ref "USB-POLY")
      (value "400mA")
      (footprint "eagle-import:F0805MP")
      (libsource (lib "eagle-import") (part "PTC-F0805MP"))
    )
    (comp (ref "VOLTAGE-METER2")
      (value "XH-2")
      (footprint "eagle-import:CON2")
      (libsource (lib "eagle-import") (part "forprint_XH-2"))
    )
    (comp (ref "X1")
      (value "RASPI_BOARD_B+#_FP")
      (footprint "eagle-import:RASPI_BOARD_B+_FULL_PAD")
      (libsource (lib "eagle-import") (part "RASPI_BOARD_B+#_FP"))
    )
    (comp (ref "X2")
      (value "DCJACK-MJ179P")
      (footprint "eagle-import:MJ-179P")
      (libsource (lib "eagle-import") (part "DCJACK-MJ179P"))
    )
    (comp (ref "X3")
      (value "C-07674_USB-A")
      (footprint "eagle-import:PN87520-S")
      (libsource (lib "eagle-import") (part "C-07674_USB-A"))
    )
    (comp (ref "X4")
      (value "AK500/2")
      (footprint "eagle-import:AK500_2")
      (libsource (lib "eagle-import") (part "AK500/2"))
    )
    (comp (ref "X5")
      (value "AK500/2")
      (footprint "eagle-import:AK500_2")
      (libsource (lib "eagle-import") (part "AK500/2"))
    )
    (comp (ref "X6")
      (value "AK500/2")
      (footprint "eagle-import:AK500_2")
      (libsource (lib "eagle-import") (part "AK500/2"))
    )
    (comp (ref "XB1")
      (value "XBEE-PRO")
      (footprint "eagle-import:XBEE-PRO")
      (fields (field (name "MPN") "XBP24-AWI-001"))
      (libsource (lib "eagle-import") (part "XBEE-PRO"))
    )
    (comp (ref "XBEE-RST")
      (value "4.7K")
      (footprint "eagle-import:R0805")
      (libsource (lib "eagle-import") (part "R-US_R0805"))
    )
  )
  (nets
    (net (code "1") (name "+3V3") (class "Default")
      (node (ref "50MHZ") (pin "4") (pinfunction "VDD_4") (pintype "power_in"))
      (node (ref "ADC1") (pin "P$2") (pinfunction "2_P$2") (pintype "bidirectional"))
      (node (ref "ADC2") (pin "P$2") (pinfunction "2_P$2") (pintype "bidirectional"))
      (node (ref "ADC3") (pin "P$2") (pinfunction "2_P$2") (pintype "bidirectional"))
      (node (ref "ADC4") (pin "P$2") (pinfunction "2_P$2") (pintype "bidirectional"))
      (node (ref "BOOT0-STM") (pin "1") (pinfunction "1_1") (pintype "passive"))
      (node (ref "BOOT0-STM") (pin "2") (pinfunction "2_2") (pintype "passive"))
      (node (ref "CN1") (pin "12") (pinfunction "LED2_A_12") (pintype "bidirectional"))
      (node (ref "CN1") (pin "3") (pinfunction "TCT_3") (pintype "bidirectional"))
      (node (ref "CN1") (pin "6") (pinfunction "RCT_6") (pintype "bidirectional"))
      (node (ref "CN1") (pin "9") (pinfunction "LED1_A_9") (pintype "bidirectional"))
      (node (ref "EM-SW") (pin "P$1") (pinfunction "1_P$1") (pintype "bidirectional"))
      (node (ref "HUMAN1") (pin "P$1") (pinfunction "1_P$1") (pintype "bidirectional"))
      (node (ref "HUMAN2") (pin "P$1") (pinfunction "1_P$1") (pintype "bidirectional"))
      (node (ref "HUMAN3") (pin "P$1") (pinfunction "1_P$1") (pintype "bidirectional"))
      (node (ref "I2C-R") (pin "P$4") (pinfunction "4_P$4") (pintype "bidirectional"))
      (node (ref "I2C-R1") (pin "1") (pinfunction "1_1") (pintype "passive"))
      (node (ref "I2C-R2") (pin "1") (pinfunction "1_1") (pintype "passive"))
      (node (ref "IC1") (pin "100") (pinfunction "VDD_100") (pintype "power_in"))
      (node (ref "IC1") (pin "11") (pinfunction "VDD_11") (pintype "power_in"))
      (node (ref "IC1") (pin "19") (pinfunction "VDD_19") (pintype "power_in"))
      (node (ref "IC1") (pin "21") (pinfunction "VREF+_21") (pintype "power_in"))
      (node (ref "IC1") (pin "22") (pinfunction "VDDA_22") (pintype "power_in"))
      (node (ref "IC1") (pin "28") (pinfunction "VDD_28") (pintype "power_in"))
      (node (ref "IC1") (pin "50") (pinfunction "VDD_50") (pintype "power_in"))
      (node (ref "IC1") (pin "6") (pinfunction "VBAT_6") (pintype "power_in"))
      (node (ref "IC1") (pin "75") (pinfunction "VDD_75") (pintype "power_in"))
      (node (ref "IC3") (pin "22") (pinfunction "ANA33VDD_22") (pintype "power_in"))
      (node (ref "IC3") (pin "32") (pinfunction "IO_VDD2_32") (pintype "power_in"))
      (node (ref "IC3") (pin "48") (pinfunction "IO_VDD1_48") (pintype "power_in"))
      (node (ref "JY901") (pin "P$4") (pinfunction "4_P$4") (pintype "bidirectional"))
      (node (ref "M-JP-VCC") (pin "1") (pinfunction "1_1") (pintype "passive"))
      (node (ref "MPU-SIG") (pin "P$6") (pinfunction "6_P$6") (pintype "bidirectional"))
      (node (ref "NT-C1") (pin "2") (pinfunction "2_2") (pintype "passive"))
      (node (ref "NT-C4") (pin "1") (pinfunction "1_1") (pintype "passive"))
      (node (ref "NT-R1") (pin "2") (pinfunction "2_2") (pintype "passive"))
      (node (ref "NT-R2") (pin "2") (pinfunction "2_2") (pintype "passive"))
      (node (ref "NT-R4") (pin "2") (pinfunction "2_2") (pintype "passive"))
      (node (ref "NT-R5") (pin "2") (pinfunction "2_2") (pintype "passive"))
      (node (ref "NT-R6") (pin "1") (pinfunction "1_1") (pintype "passive"))
      (node (ref "NT-R7") (pin "2") (pinfunction "2_2") (pintype "passive"))
      (node (ref "NT-R8") (pin "2") (pinfunction "2_2") (pintype "passive"))
      (node (ref "NT-R9") (pin "1") (pinfunction "1_1") (pintype "passive"))
      (node (ref "NT-RST-R") (pin "2") (pinfunction "2_2") (pintype "passive"))
      (node (ref "Q2") (pin "D") (pinfunction "D_D") (pintype "passive"))
      (node (ref "RO-R") (pin "1") (pinfunction "1_1") (pintype "passive"))
      (node (ref "RO-R") (pin "2") (pinfunction "1_2") (pintype "passive"))
      (node (ref "RO-R") (pin "3") (pinfunction "1_3") (pintype "passive"))
      (node (ref "RO-R") (pin "4") (pinfunction "1_4") (pintype "passive"))
      (node (ref "S2") (pin "1") (pinfunction "O_1") (pintype "passive"))
      (node (ref "SP-LED2") (pin "A") (pinfunction "A_A") (pintype "passive"))
      (node (ref "SPI-R") (pin "P$6") (pinfunction "6_P$6") (pintype "bidirectional"))
      (node (ref "ST-LINKV2") (pin "1") (pinfunction "1_1") (pintype "passive"))
      (node (ref "STM-C1") (pin "2") (pinfunction "2_2") (pintype "passive"))
      (node (ref "STM-C2") (pin "2") (pinfunction "2_2") (pintype "passive"))
      (node (ref "STM-C3") (pin "2") (pinfunction "2_2") (pintype "passive"))
      (node (ref "STM-C4") (pin "2") (pinfunction "2_2") (pintype "passive"))
      (node (ref "STM-C7") (pin "2") (pinfunction "2_2") (pintype "passive"))
      (node (ref "STM-R1") (pin "2") (pinfunction "2_2") (pintype "passive"))
      (node (ref "X5") (pin "1") (pinfunction "KL_1") (pintype "passive"))
      (node (ref "XB1") (pin "1") (pinfunction "VCC_1") (pintype "power_in"))
      (node (ref "XB1") (pin "14") (pinfunction "VREF_14") (pintype "input"))
      (node (ref "XBEE-RST") (pin "2") (pinfunction "2_2") (pintype "passive"))
    )
    (net (code "2") (name "+3V3S") (class "Default")
      (node (ref "3.3C1") (pin "+") (pinfunction "+_+") (pintype "passive"))
      (node (ref "3.3C2") (pin "1") (pinfunction "1_1") (pintype "passive"))
      (node (ref "3.3REG") (pin "4") (pinfunction "VOUT_4") (pintype "bidirectional"))
      (node (ref "3.3REG") (pin "5") (pinfunction "SENSE_5") (pintype "bidirectional"))
      (node (ref "C4") (pin "1") (pinfunction "1_1") (pintype "passive"))
      (node (ref "Q2") (pin "S") (pinfunction "S_S") (pintype "passive"))
      (node (ref "R2") (pin "1") (pinfunction "1_1") (pintype "passive"))
      (node (ref "SP-R7") (pin "2") (pinfunction "2_2") (pintype "passive"))
      (node (ref "TO-UI3") (pin "12") (pinfunction "12_12") (pintype "passive"))
    )
    (net (code "3") (name "+5V") (class "Default")
      (node (ref "Q4") (pin "D") (pinfunction "D_D") (pintype "passive"))
      (node (ref "RP-C1") (pin "2") (pinfunction "2_2") (pintype "passive"))
      (node (ref "RP-C2") (pin "2") (pinfunction "2_2") (pintype "passive"))
      (node (ref "S2") (pin "3") (pinfunction "S_3") (pintype "passive"))
      (node (ref "SJ1") (pin "3") (pinfunction "3_3") (pintype "passive"))
      (node (ref "SJ2") (pin "3") (pinfunction "3_3") (pintype "passive"))
      (node (ref "SJ3") (pin "3") (pinfunction "3_3") (pintype "passive"))
      (node (ref "SJ4") (pin "3") (pinfunction "3_3") (pintype "passive"))
      (node (ref "SP-LED1") (pin "A") (pinfunction "A_A") (pintype "passive"))
      (node (ref "X1") (pin "2") (pinfunction "5V0A_2") (pintype "power_in"))
      (node (ref "X1") (pin "4") (pinfunction "5V0B_4") (pintype "power_in"))
      (node (ref "X4") (pin "1") (pinfunction "KL_1") (pintype "passive"))
    )
    (net (code "4") (name "+5VS") (class "Default")
      (node (ref "5C1") (pin "+") (pinfunction "+_+") (pintype "passive"))
      (node (ref "5C2") (pin "1") (pinfunction "1_1") (pintype "passive"))
      (node (ref "5VREG") (pin "4") (pinfunction "VOUT_4") (pintype "bidirectional"))
      (node (ref "5VREG") (pin "5") (pinfunction "SENSE_5") (pintype "bidirectional"))
      (node (ref "5VS-C1") (pin "1") (pinfunction "1_1") (pintype "passive"))
      (node (ref "C2") (pin "1") (pinfunction "1_1") (pintype "passive"))
      (node (ref "IC1") (pin "55") (pinfunction "PD8_55") (pintype "bidirectional"))
      (node (ref "IC2") (pin "8") (pinfunction "VCC_8") (pintype "input"))
      (node (ref "IC4") (pin "3") (pinfunction "VDD_3") (pintype "bidirectional"))
      (node (ref "JP1") (pin "1") (pinfunction "1_1") (pintype "passive"))
      (node (ref "PING") (pin "P$2") (pinfunction "2_P$2") (pintype "bidirectional"))
      (node (ref "Q4") (pin "S") (pinfunction "S_S") (pintype "passive"))
      (node (ref "R1") (pin "1") (pinfunction "1_1") (pintype "passive"))
      (node (ref "RO1") (pin "P$1") (pinfunction "1_P$1") (pintype "bidirectional"))
      (node (ref "RO2") (pin "P$1") (pinfunction "1_P$1") (pintype "bidirectional"))
      (node (ref "ROUTER") (pin "1") (pinfunction "KL_1") (pintype "passive"))
      (node (ref "SP-R8") (pin "2") (pinfunction "2_2") (pintype "passive"))
      (node (ref "TO-UI3") (pin "7") (pinfunction "7_7") (pintype "passive"))
      (node (ref "USB-POLY") (pin "1") (pinfunction "1_1") (pintype "passive"))
    )
    (net (code "5") (name "+12V") (class "Default")
      (node (ref "12C2") (pin "1") (pinfunction "1_1") (pintype "passive"))
      (node (ref "3.3REG") (pin "2") (pinfunction "VIN_2") (pintype "bidirectional"))
      (node (ref "5VREG") (pin "2") (pinfunction "VIN_2") (pintype "bidirectional"))
      (node (ref "9C1") (pin "+") (pinfunction "+_+") (pintype "passive"))
      (node (ref "C1") (pin "1") (pinfunction "1_1") (pintype "passive"))
      (node (ref "C3") (pin "1") (pinfunction "1_1") (pintype "passive"))
      (node (ref "LED5") (pin "1") (pinfunction "1_1") (pintype "passive"))
      (node (ref "LED6") (pin "1") (pinfunction "1_1") (pintype "passive"))
      (node (ref "LED7") (pin "1") (pinfunction "1_1") (pintype "passive"))
      (node (ref "LED8") (pin "1") (pinfunction "1_1") (pintype "passive"))
      (node (ref "MAIN-SPL") (pin "P$1") (pinfunction "1_P$1") (pintype "bidirectional"))
      (node (ref "Q5") (pin "D") (pinfunction "D_D") (pintype "passive"))
      (node (ref "SJ1") (pin "1") (pinfunction "1_1") (pintype "passive"))
      (node (ref "SJ2") (pin "1") (pinfunction "1_1") (pintype "passive"))
      (node (ref "SJ3") (pin "1") (pinfunction "1_1") (pintype "passive"))
      (node (ref "SJ4") (pin "1") (pinfunction "1_1") (pintype "passive"))
      (node (ref "SP-R2") (pin "2") (pinfunction "2_2") (pintype "passive"))
      (node (ref "SP-R4") (pin "2") (pinfunction "2_2") (pintype "passive"))
      (node (ref "TO-F7") (pin "14") (pinfunction "14_14") (pintype "passive"))
      (node (ref "TO-UI3") (pin "14") (pinfunction "14_14") (pintype "passive"))
      (node (ref "X6") (pin "1") (pinfunction "KL_1") (pintype "passive"))
    )
    (net (code "6") (name "+12VS") (class "Default")
      (node (ref "Q3") (pin "S") (pinfunction "S_S") (pintype "passive"))
      (node (ref "Q5") (pin "S") (pinfunction "S_S") (pintype "passive"))
      (node (ref "SP-R6") (pin "2") (pinfunction "2_2") (pintype "passive"))
      (node (ref "TO-UI3") (pin "3") (pinfunction "3_3") (pintype "passive"))
    )
    (net (code "7") (name "/3V3A") (class "Default")
      (node (ref "X1") (pin "1") (pinfunction "3V3A_1") (pintype "power_in"))
    )
    (net (code "8") (name "/3V3B") (class "Default")
      (node (ref "X1") (pin "17") (pinfunction "3V3B_17") (pintype "power_in"))
    )
    (net (code "9") (name "3V3-SW") (class "Default")
      (node (ref "Q2") (pin "G") (pinfunction "G_G") (pintype "passive"))
      (node (ref "S3") (pin "1") (pinfunction "O_1") (pintype "passive"))
      (node (ref "SP-R7") (pin "1") (pinfunction "1_1") (pintype "passive"))
      (node (ref "TO-UI3") (pin "6") (pinfunction "6_6") (pintype "passive"))
    )
    (net (code "10") (name "5V-SW") (class "Default")
      (node (ref "Q4") (pin "G") (pinfunction "G_G") (pintype "passive"))
      (node (ref "S1") (pin "1") (pinfunction "O_1") (pintype "passive"))
      (node (ref "SP-R8") (pin "1") (pinfunction "1_1") (pintype "passive"))
      (node (ref "TO-UI3") (pin "5") (pinfunction "5_5") (pintype "passive"))
    )
    (net (code "11") (name "12V-SW") (class "Default")
      (node (ref "MAINSW2") (pin "1") (pinfunction "1_1") (pintype "passive"))
      (node (ref "Q5") (pin "G") (pinfunction "G_G") (pintype "passive"))
      (node (ref "SP-R6") (pin "1") (pinfunction "1_1") (pintype "passive"))
      (node (ref "SUOPPLY-SW2") (pin "P$1") (pinfunction "1_P$1") (pintype "bidirectional"))
      (node (ref "TO-UI3") (pin "4") (pinfunction "4_4") (pintype "passive"))
    )
    (net (code "12") (name "ADC1") (class "Default")
      (node (ref "ADC1") (pin "P$1") (pinfunction "1_P$1") (pintype "bidirectional"))
      (node (ref "IC1") (pin "36") (pinfunction "PB1_36") (pintype "bidirectional"))
    )
    (net (code "13") (name "ADC2") (class "Default")
      (node (ref "ADC2") (pin "P$1") (pinfunction "1_P$1") (pintype "bidirectional"))
      (node (ref "IC1") (pin "35") (pinfunction "PB0_35") (pintype "bidirectional"))
    )
    (net (code "14") (name "ADC3") (class "Default")
      (node (ref "ADC3") (pin "P$1") (pinfunction "1_P$1") (pintype "bidirectional"))
      (node (ref "IC1") (pin "18") (pinfunction "PC3_18") (pintype "bidirectional"))
    )
    (net (code "15") (name "ADC4") (class "Default")
      (node (ref "ADC4") (pin "P$1") (pinfunction "1_P$1") (pintype "bidirectional"))
      (node (ref "IC1") (pin "17") (pinfunction "PC2_17") (pintype "bidirectional"))
    )
    (net (code "16") (name "BOOT-RX") (class "Default")
      (node (ref "IC1") (pin "69") (pinfunction "PA10_69") (pintype "bidirectional"))
      (node (ref "XB1") (pin "2") (pinfunction "DOUT_2") (pintype "output"))
    )
    (net (code "17") (name "BOOT-TX") (class "Default")
      (node (ref "IC1") (pin "68") (pinfunction "PA9_68") (pintype "bidirectional"))
      (node (ref "XB1") (pin "3") (pinfunction "DIN/~{CONFIG}_3") (pintype "input"))
    )
    (net (code "18") (name "BOOT0") (class "Default")
      (node (ref "BOOT0-STM") (pin "3") (pinfunction "3_3") (pintype "passive"))
      (node (ref "BOOT0-STM") (pin "4") (pinfunction "4_4") (pintype "passive"))
      (node (ref "IC1") (pin "94") (pinfunction "BOOT0_94") (pintype "input"))
      (node (ref "STM-R2") (pin "1") (pinfunction "1_1") (pintype "passive"))
      (node (ref "TO-UI3") (pin "8") (pinfunction "8_8") (pintype "passive"))
    )
    (net (code "19") (name "BUZZER1") (class "Default")
      (node (ref "BUZ-R1") (pin "1") (pinfunction "1_1") (pintype "passive"))
      (node (ref "IC1") (pin "59") (pinfunction "PD12_59") (pintype "bidirectional"))
      (node (ref "SG1") (pin "1") (pinfunction "1_1") (pintype "passive"))
    )
    (net (code "20") (name "BUZZER2") (class "Default")
      (node (ref "BUZ-R2") (pin "1") (pinfunction "1_1") (pintype "passive"))
      (node (ref "BUZZER2") (pin "P$2") (pinfunction "2_P$2") (pintype "bidirectional"))
      (node (ref "IC1") (pin "60") (pinfunction "PD13_60") (pintype "bidirectional"))
    )
    (net (code "21") (name "CAN-H") (class "Default")
      (node (ref "CAN-R") (pin "P$2") (pinfunction "2_P$2") (pintype "bidirectional"))
      (node (ref "CAN-R1") (pin "2") (pinfunction "2_2") (pintype "passive"))
      (node (ref "IC4") (pin "7") (pinfunction "CANH_7") (pintype "bidirectional"))
      (node (ref "TO-F7") (pin "8") (pinfunction "8_8") (pintype "passive"))
    )
    (net (code "22") (name "CAN-L") (class "Default")
      (node (ref "CAN-R") (pin "P$1") (pinfunction "1_P$1") (pintype "bidirectional"))
      (node (ref "CAN-R2") (pin "2") (pinfunction "2_2") (pintype "passive"))
      (node (ref "IC4") (pin "6") (pinfunction "CANL_6") (pintype "bidirectional"))
      (node (ref "TO-F7") (pin "7") (pinfunction "7_7") (pintype "passive"))
    )
    (net (code "23") (name "CAN-RX") (class "Default")
      (node (ref "IC1") (pin "91") (pinfunction "PB5_91") (pintype "bidirectional"))
      (node (ref "IC4") (pin "1") (pinfunction "TXD_1") (pintype "bidirectional"))
    )
    (net (code "24") (name "CAN-TX") (class "Default")
      (node (ref "IC1") (pin "92") (pinfunction "PB6_92") (pintype "bidirectional"))
      (node (ref "IC4") (pin "4") (pinfunction "RXD_4") (pintype "bidirectional"))
    )
    (net (code "25") (name "EMERGENCY") (class "Default")
      (node (ref "EM-SW") (pin "P$2") (pinfunction "2_P$2") (pintype "bidirectional"))
      (node (ref "IC1") (pin "15") (pinfunction "PC0_15") (pintype "bidirectional"))
      (node (ref "SW-R1") (pin "1") (pinfunction "1_1") (pintype "passive"))
      (node (ref "TO-F7") (pin "3") (pinfunction "3_3") (pintype "passive"))
      (node (ref "X1") (pin "29") (pinfunction "GPIO05_29") (pintype "bidirectional"))
    )
    (net (code "26") (name "ETH_CRS_DV") (class "Default")
      (node (ref "IC1") (pin "32") (pinfunction "PA7_32") (pintype "bidirectional"))
      (node (ref "IC3") (pin "40") (pinfunction "CRS_40") (pintype "bidirectional"))
      (node (ref "NT-R1") (pin "1") (pinfunction "1_1") (pintype "passive"))
    )
    (net (code "27") (name "ETH_MDC") (class "Default")
      (node (ref "IC1") (pin "16") (pinfunction "PC1_16") (pintype "bidirectional"))
      (node (ref "IC3") (pin "31") (pinfunction "MDC_31") (pintype "input"))
    )
    (net (code "28") (name "ETH_MDIO") (class "Default")
      (node (ref "IC1") (pin "25") (pinfunction "PA2_25") (pintype "bidirectional"))
      (node (ref "IC3") (pin "30") (pinfunction "MDIO_30") (pintype "bidirectional"))
    )
    (net (code "29") (name "ETH_REF_CLK") (class "Default")
      (node (ref "IC1") (pin "24") (pinfunction "PA1_24") (pintype "bidirectional"))
      (node (ref "IC3") (pin "34") (pinfunction "X1_34") (pintype "input"))
      (node (ref "NT-JP") (pin "1") (pinfunction "1_1") (pintype "passive"))
    )
    (net (code "30") (name "ETH_RXD0") (class "Default")
      (node (ref "IC1") (pin "33") (pinfunction "PC4_33") (pintype "bidirectional"))
      (node (ref "IC3") (pin "43") (pinfunction "RXD_0_43") (pintype "bidirectional"))
    )
    (net (code "31") (name "ETH_RXD1") (class "Default")
      (node (ref "IC1") (pin "34") (pinfunction "PC5_34") (pintype "bidirectional"))
      (node (ref "IC3") (pin "44") (pinfunction "RXD_1_44") (pintype "bidirectional"))
    )
    (net (code "32") (name "ETH_TXD0") (class "Default")
      (node (ref "IC1") (pin "51") (pinfunction "PB12_51") (pintype "bidirectional"))
      (node (ref "IC3") (pin "3") (pinfunction "TXD_0_3") (pintype "bidirectional"))
    )
    (net (code "33") (name "ETH_TXD1") (class "Default")
      (node (ref "IC1") (pin "52") (pinfunction "PB13_52") (pintype "bidirectional"))
      (node (ref "IC3") (pin "4") (pinfunction "TXD_1_4") (pintype "bidirectional"))
    )
    (net (code "34") (name "ETH_TX_EN") (class "Default")
      (node (ref "IC1") (pin "48") (pinfunction "PB11_48") (pintype "bidirectional"))
      (node (ref "IC3") (pin "2") (pinfunction "TX_EN_2") (pintype "bidirectional"))
    )
    (net (code "35") (name "F7-F4-SIG1") (class "Default")
      (node (ref "IC1") (pin "84") (pinfunction "PD3_84") (pintype "bidirectional"))
      (node (ref "TO-F7") (pin "12") (pinfunction "12_12") (pintype "passive"))
    )
    (net (code "36") (name "F7-F4-SIG2") (class "Default")
      (node (ref "IC1") (pin "83") (pinfunction "PD2_83") (pintype "bidirectional"))
      (node (ref "TO-F7") (pin "11") (pinfunction "11_11") (pintype "passive"))
    )
    (net (code "37") (name "F7-RS-SIG1") (class "Default")
      (node (ref "TO-F7") (pin "10") (pinfunction "10_10") (pintype "passive"))
      (node (ref "X1") (pin "11") (pinfunction "GPIO17_11") (pintype "bidirectional"))
    )
    (net (code "38") (name "F7-RS-SIG2") (class "Default")
      (node (ref "TO-F7") (pin "9") (pinfunction "9_9") (pintype "passive"))
      (node (ref "X1") (pin "13") (pinfunction "GPIO27_13") (pintype "bidirectional"))
    )
    (net (code "39") (name "FET1") (class "Default")
      (node (ref "IC1") (pin "9") (pinfunction "PC15_9") (pintype "bidirectional"))
      (node (ref "LED1") (pin "2") (pinfunction "2_2") (pintype "passive"))
    )
    (net (code "40") (name "FET2") (class "Default")
      (node (ref "IC1") (pin "8") (pinfunction "PC14_8") (pintype "bidirectional"))
      (node (ref "LED2") (pin "2") (pinfunction "2_2") (pintype "passive"))
    )
    (net (code "41") (name "FET3") (class "Default")
      (node (ref "IC1") (pin "7") (pinfunction "PC13_7") (pintype "bidirectional"))
      (node (ref "LED3") (pin "2") (pinfunction "2_2") (pintype "passive"))
    )
    (net (code "42") (name "FET4") (class "Default")
      (node (ref "IC1") (pin "5") (pinfunction "PE6_5") (pintype "bidirectional"))
      (node (ref "LED4") (pin "2") (pinfunction "2_2") (pintype "passive"))
    )
    (net (code "43") (name "FET5") (class "Default")
      (node (ref "FET-R9") (pin "2") (pinfunction "2_2") (pintype "passive"))
      (node (ref "IC1") (pin "4") (pinfunction "PE5_4") (pintype "bidirectional"))
    )
    (net (code "44") (name "FET6") (class "Default")
      (node (ref "FET-R10") (pin "2") (pinfunction "2_2") (pintype "passive"))
      (node (ref "IC1") (pin "3") (pinfunction "PE4_3") (pintype "bidirectional"))
    )
    (net (code "45") (name "FET7") (class "Default")
      (node (ref "FET-R13") (pin "2") (pinfunction "2_2") (pintype "passive"))
      (node (ref "IC1") (pin "2") (pinfunction "PE3_2") (pintype "bidirectional"))
    )
    (net (code "46") (name "FET8") (class "Default")
      (node (ref "FET-R14") (pin "2") (pinfunction "2_2") (pintype "passive"))
      (node (ref "IC1") (pin "1") (pinfunction "PE2_1") (pintype "bidirectional"))
    )
    (net (code "47") (name "GND") (class "Default")
      (node (ref "100") (pin "1") (pinfunction "1_1") (pintype "passive"))
      (node (ref "12C2") (pin "2") (pinfunction "2_2") (pintype "passive"))
      (node (ref "3.3C1") (pin "-") (pinfunction "-_-") (pintype "passive"))
      (node (ref "3.3C2") (pin "2") (pinfunction "2_2") (pintype "passive"))
      (node (ref "3.3REG") (pin "3") (pinfunction "GND_1_3") (pintype "bidirectional"))
      (node (ref "3.3REG") (pin "7") (pinfunction "GND_2_7") (pintype "bidirectional"))
      (node (ref "50MHZ") (pin "2") (pinfunction "GND_2") (pintype "power_in"))
      (node (ref "5C1") (pin "-") (pinfunction "-_-") (pintype "passive"))
      (node (ref "5C2") (pin "2") (pinfunction "2_2") (pintype "passive"))
      (node (ref "5VREG") (pin "3") (pinfunction "GND_1_3") (pintype "bidirectional"))
      (node (ref "5VREG") (pin "7") (pinfunction "GND_2_7") (pintype "bidirectional"))
      (node (ref "5VS-C1") (pin "2") (pinfunction "2_2") (pintype "passive"))
      (node (ref "9C1") (pin "-") (pinfunction "-_-") (pintype "passive"))
      (node (ref "ADC1") (pin "P$3") (pinfunction "3_P$3") (pintype "bidirectional"))
      (node (ref "ADC2") (pin "P$3") (pinfunction "3_P$3") (pintype "bidirectional"))
      (node (ref "ADC3") (pin "P$3") (pinfunction "3_P$3") (pintype "bidirectional"))
      (node (ref "ADC4") (pin "P$3") (pinfunction "3_P$3") (pintype "bidirectional"))
      (node (ref "BAT-R2") (pin "2") (pinfunction "2_2") (pintype "passive"))
      (node (ref "BUZ-R1") (pin "2") (pinfunction "2_2") (pintype "passive"))
      (node (ref "BUZ-R2") (pin "2") (pinfunction "2_2") (pintype "passive"))
      (node (ref "BUZZER2") (pin "P$1") (pinfunction "1_P$1") (pintype "bidirectional"))
      (node (ref "C1") (pin "2") (pinfunction "2_2") (pintype "passive"))
      (node (ref "C2") (pin "2") (pinfunction "2_2") (pintype "passive"))
      (node (ref "C3") (pin "2") (pinfunction "2_2") (pintype "passive"))
      (node (ref "C4") (pin "2") (pinfunction "2_2") (pintype "passive"))
      (node (ref "C5") (pin "1") (pinfunction "1_1") (pintype "passive"))
      (node (ref "C6") (pin "1") (pinfunction "1_1") (pintype "passive"))
      (node (ref "CAN-C1") (pin "1") (pinfunction "1_1") (pintype "passive"))
      (node (ref "CN1") (pin "4") (pinfunction "GND1_4") (pintype "bidirectional"))
      (node (ref "CN1") (pin "5") (pinfunction "GND2_5") (pintype "bidirectional"))
      (node (ref "FETR2") (pin "1") (pinfunction "1_1") (pintype "passive"))
      (node (ref "FETR2") (pin "2") (pinfunction "1_2") (pintype "passive"))
      (node (ref "FETR2") (pin "3") (pinfunction "1_3") (pintype "passive"))
      (node (ref "FETR2") (pin "4") (pinfunction "1_4") (pintype "passive"))
      (node (ref "GND-CH") (pin "1") (pinfunction "P_1") (pintype "passive"))
      (node (ref "GND-CHK") (pin "1") (pinfunction "P_1") (pintype "passive"))
      (node (ref "GND-CHK1") (pin "1") (pinfunction "P_1") (pintype "passive"))
      (node (ref "HUMAN1") (pin "P$3") (pinfunction "3_P$3") (pintype "bidirectional"))
      (node (ref "HUMAN2") (pin "P$3") (pinfunction "3_P$3") (pintype "bidirectional"))
      (node (ref "HUMAN3") (pin "P$3") (pinfunction "3_P$3") (pintype "bidirectional"))
      (node (ref "I2C-R") (pin "P$1") (pinfunction "1_P$1") (pintype "bidirectional"))
      (node (ref "IC1") (pin "10") (pinfunction "VSS_10") (pintype "power_in"))
      (node (ref "IC1") (pin "20") (pinfunction "VSSA_20") (pintype "power_in"))
      (node (ref "IC1") (pin "27") (pinfunction "VSS_27") (pintype "power_in"))
      (node (ref "IC1") (pin "74") (pinfunction "VSS_74") (pintype "power_in"))
      (node (ref "IC1") (pin "99") (pinfunction "VSS_99") (pintype "power_in"))
      (node (ref "IC2") (pin "5") (pinfunction "GND_5") (pintype "input"))
      (node (ref "IC3") (pin "15") (pinfunction "CDVSS_15") (pintype "power_in"))
      (node (ref "IC3") (pin "19") (pinfunction "ANA18VSS_19") (pintype "power_in"))
      (node (ref "IC3") (pin "35") (pinfunction "IO_VSS2_35") (pintype "power_in"))
      (node (ref "IC3") (pin "36") (pinfunction "CORE_VSS_36") (pintype "power_in"))
      (node (ref "IC3") (pin "47") (pinfunction "IO_VSS1_47") (pintype "power_in"))
      (node (ref "IC4") (pin "2") (pinfunction "VSS_2") (pintype "bidirectional"))
      (node (ref "IC4") (pin "8") (pinfunction "STBY_8") (pintype "bidirectional"))
      (node (ref "JP1") (pin "2") (pinfunction "2_2") (pintype "passive"))
      (node (ref "JY901") (pin "P$1") (pinfunction "1_P$1") (pintype "bidirectional"))
      (node (ref "LED1") (pin "3") (pinfunction "3_3") (pintype "passive"))
      (node (ref "LED2") (pin "3") (pinfunction "3_3") (pintype "passive"))
      (node (ref "LED3") (pin "3") (pinfunction "3_3") (pintype "passive"))
      (node (ref "LED4") (pin "3") (pinfunction "3_3") (pintype "passive"))
      (node (ref "LIPO") (pin "2") (pinfunction "2_2") (pintype "passive"))
      (node (ref "M-JP-GND") (pin "2") (pinfunction "2_2") (pintype "passive"))
      (node (ref "MAIN-SPL") (pin "P$2") (pinfunction "2_P$2") (pintype "bidirectional"))
      (node (ref "MAINSW2") (pin "2") (pinfunction "2_2") (pintype "passive"))
      (node (ref "MPU-SIG") (pin "P$2") (pinfunction "2_P$2") (pintype "bidirectional"))
      (node (ref "NT-C1") (pin "1") (pinfunction "1_1") (pintype "passive"))
      (node (ref "NT-C3") (pin "1") (pinfunction "1_1") (pintype "passive"))
      (node (ref "NT-C4") (pin "2") (pinfunction "2_2") (pintype "passive"))
      (node (ref "NT-C5") (pin "2") (pinfunction "2_2") (pintype "passive"))
      (node (ref "NT-R3") (pin "1") (pinfunction "1_1") (pintype "passive"))
      (node (ref "PING") (pin "P$3") (pinfunction "3_P$3") (pintype "bidirectional"))
      (node (ref "Q3") (pin "G") (pinfunction "G_G") (pintype "passive"))
      (node (ref "R1") (pin "2") (pinfunction "2_2") (pintype "passive"))
      (node (ref "R2") (pin "2") (pinfunction "2_2") (pintype "passive"))
      (node (ref "RESET-STM") (pin "1") (pinfunction "1_1") (pintype "passive"))
      (node (ref "RESET-STM") (pin "2") (pinfunction "2_2") (pintype "passive"))
      (node (ref "RO1") (pin "P$2") (pinfunction "2_P$2") (pintype "bidirectional"))
      (node (ref "RO1") (pin "P$5") (pinfunction "5_P$5") (pintype "bidirectional"))
      (node (ref "RO2") (pin "P$2") (pinfunction "2_P$2") (pintype "bidirectional"))
      (node (ref "RO2") (pin "P$5") (pinfunction "5_P$5") (pintype "bidirectional"))
      (node (ref "ROUTER") (pin "2") (pinfunction "KL_2") (pintype "passive"))
      (node (ref "RP-C1") (pin "1") (pinfunction "1_1") (pintype "passive"))
      (node (ref "RP-C2") (pin "1") (pinfunction "1_1") (pintype "passive"))
      (node (ref "S1") (pin "2") (pinfunction "P_2") (pintype "passive"))
      (node (ref "S3") (pin "2") (pinfunction "P_2") (pintype "passive"))
      (node (ref "S4") (pin "1") (pinfunction "1_1") (pintype "bidirectional"))
      (node (ref "S4") (pin "2") (pinfunction "2_2") (pintype "bidirectional"))
      (node (ref "S5") (pin "3") (pinfunction "3_3") (pintype "bidirectional"))
      (node (ref "S5") (pin "4") (pinfunction "4_4") (pintype "bidirectional"))
      (node (ref "SG1") (pin "2") (pinfunction "2_2") (pintype "passive"))
      (node (ref "SJ5") (pin "1") (pinfunction "1_1") (pintype "passive"))
      (node (ref "SJ6") (pin "1") (pinfunction "1_1") (pintype "passive"))
      (node (ref "SP-R1") (pin "1") (pinfunction "1_1") (pintype "passive"))
      (node (ref "SP-R3") (pin "1") (pinfunction "1_1") (pintype "passive"))
      (node (ref "SP-R5") (pin "1") (pinfunction "1_1") (pintype "passive"))
      (node (ref "SPI-R") (pin "P$2") (pinfunction "2_P$2") (pintype "bidirectional"))
      (node (ref "ST-LINKV2") (pin "3") (pinfunction "3_3") (pintype "passive"))
      (node (ref "STM-C1") (pin "1") (pinfunction "1_1") (pintype "passive"))
      (node (ref "STM-C2") (pin "1") (pinfunction "1_1") (pintype "passive"))
      (node (ref "STM-C3") (pin "1") (pinfunction "1_1") (pintype "passive"))
      (node (ref "STM-C4") (pin "1") (pinfunction "1_1") (pintype "passive"))
      (node (ref "STM-C5") (pin "2") (pinfunction "2_2") (pintype "passive"))
      (node (ref "STM-C6") (pin "2") (pinfunction "2_2") (pintype "passive"))
      (node (ref "STM-C7") (pin "1") (pinfunction "1_1") (pintype "passive"))
      (node (ref "STM-R2") (pin "2") (pinfunction "2_2") (pintype "passive"))
      (node (ref "SUOPPLY-SW2") (pin "P$2") (pinfunction "2_P$2") (pintype "bidirectional"))
      (node (ref "SW-R1") (pin "2") (pinfunction "2_2") (pintype "passive"))
      (node (ref "T3") (pin "1") (pinfunction "S_1") (pintype "passive"))
      (node (ref "T3") (pin "3") (pinfunction "S_3") (pintype "passive"))
      (node (ref "T4") (pin "1") (pinfunction "S_1") (pintype "passive"))
      (node (ref "T4") (pin "3") (pinfunction "S_3") (pintype "passive"))
      (node (ref "TO-F7") (pin "2") (pinfunction "2_2") (pintype "passive"))
      (node (ref "TO-UI3") (pin "13") (pinfunction "13_13") (pintype "passive"))
      (node (ref "U$2") (pin "-") (pinfunction "GND_-") (pintype "bidirectional"))
      (node (ref "VOLTAGE-METER2") (pin "P$2") (pinfunction "2_P$2") (pintype "bidirectional"))
      (node (ref "X1") (pin "14") (pinfunction "GND_C_14") (pintype "power_in"))
      (node (ref "X1") (pin "20") (pinfunction "GND_D_20") (pintype "power_in"))
      (node (ref "X1") (pin "25") (pinfunction "GND_E_25") (pintype "power_in"))
      (node (ref "X1") (pin "30") (pinfunction "GND_F_30") (pintype "power_in"))
      (node (ref "X1") (pin "34") (pinfunction "GND_G_34") (pintype "power_in"))
      (node (ref "X1") (pin "39") (pinfunction "GND_H_39") (pintype "power_in"))
      (node (ref "X1") (pin "6") (pinfunction "GND_A_6") (pintype "power_in"))
      (node (ref "X1") (pin "9") (pinfunction "GND_B_9") (pintype "power_in"))
      (node (ref "X2") (pin "2") (pinfunction "2_2") (pintype "passive"))
      (node (ref "X3") (pin "4") (pinfunction "4_4") (pintype "passive"))
      (node (ref "X3") (pin "S1") (pinfunction "S1_S1") (pintype "passive"))
      (node (ref "X3") (pin "S2") (pinfunction "S2_S2") (pintype "passive"))
      (node (ref "X4") (pin "2") (pinfunction "KL_2") (pintype "passive"))
      (node (ref "X5") (pin "2") (pinfunction "KL_2") (pintype "passive"))
      (node (ref "X6") (pin "2") (pinfunction "KL_2") (pintype "passive"))
      (node (ref "XB1") (pin "10") (pinfunction "GND_10") (pintype "power_in"))
    )
    (net (code "48") (name "HUMAN1") (class "Default")
      (node (ref "HUMAN1") (pin "P$2") (pinfunction "2_P$2") (pintype "bidirectional"))
      (node (ref "IC1") (pin "56") (pinfunction "PD9_56") (pintype "bidirectional"))
      (node (ref "TO-F7") (pin "4") (pinfunction "4_4") (pintype "passive"))
    )
    (net (code "49") (name "HUMAN2") (class "Default")
      (node (ref "HUMAN2") (pin "P$2") (pinfunction "2_P$2") (pintype "bidirectional"))
      (node (ref "IC1") (pin "57") (pinfunction "PD10_57") (pintype "bidirectional"))
    )
    (net (code "50") (name "HUMAN3") (class "Default")
      (node (ref "HUMAN3") (pin "P$2") (pinfunction "2_P$2") (pintype "bidirectional"))
      (node (ref "IC1") (pin "58") (pinfunction "PD11_58") (pintype "bidirectional"))
    )
    (net (code "51") (name "LED5") (class "Default")
      (node (ref "LED5") (pin "2") (pinfunction "2_2") (pintype "passive"))
      (node (ref "T3") (pin "7") (pinfunction "D_7") (pintype "passive"))
      (node (ref "T3") (pin "8") (pinfunction "D_8") (pintype "passive"))
    )
    (net (code "52") (name "LED6") (class "Default")
      (node (ref "LED6") (pin "2") (pinfunction "2_2") (pintype "passive"))
      (node (ref "T3") (pin "5") (pinfunction "D_5") (pintype "passive"))
      (node (ref "T3") (pin "6") (pinfunction "D_6") (pintype "passive"))
    )
    (net (code "53") (name "LED7") (class "Default")
      (node (ref "LED7") (pin "2") (pinfunction "2_2") (pintype "passive"))
      (node (ref "T4") (pin "7") (pinfunction "D_7") (pintype "passive"))
      (node (ref "T4") (pin "8") (pinfunction "D_8") (pintype "passive"))
    )
    (net (code "54") (name "LED8") (class "Default")
      (node (ref "LED8") (pin "2") (pinfunction "2_2") (pintype "passive"))
      (node (ref "T4") (pin "5") (pinfunction "D_5") (pintype "passive"))
      (node (ref "T4") (pin "6") (pinfunction "D_6") (pintype "passive"))
    )
    (net (code "55") (name "LEDACT_LINK") (class "Default")
      (node (ref "IC3") (pin "26") (pinfunction "LED_ACTCOL_26") (pintype "bidirectional"))
      (node (ref "NT-R10") (pin "1") (pinfunction "1_1") (pintype "passive"))
    )
    (net (code "56") (name "LED_LINK") (class "Default")
      (node (ref "IC3") (pin "28") (pinfunction "LED_LNK_28") (pintype "bidirectional"))
      (node (ref "NT-R11") (pin "1") (pinfunction "1_1") (pintype "passive"))
    )
    (net (code "57") (name "LIPO") (class "Default")
      (node (ref "BAT-R1") (pin "1") (pinfunction "1_1") (pintype "passive"))
      (node (ref "LIPO") (pin "1") (pinfunction "1_1") (pintype "passive"))
      (node (ref "TO-F7") (pin "13") (pinfunction "13_13") (pintype "passive"))
      (node (ref "TO-UI3") (pin "1") (pinfunction "1_1") (pintype "passive"))
    )
    (net (code "58") (name "LTC-SIG") (class "Default")
      (node (ref "IC1") (pin "85") (pinfunction "PD4_85") (pintype "bidirectional"))
      (node (ref "IC2") (pin "2") (pinfunction "~{RE}_2") (pintype "input"))
      (node (ref "IC2") (pin "3") (pinfunction "DE_3") (pintype "input"))
    )
    (net (code "59") (name "MISO") (class "Default")
      (node (ref "IC1") (pin "79") (pinfunction "PC11_79") (pintype "bidirectional"))
      (node (ref "MPU-SIG") (pin "P$4") (pinfunction "4_P$4") (pintype "bidirectional"))
      (node (ref "SPI-R") (pin "P$4") (pinfunction "4_P$4") (pintype "bidirectional"))
    )
    (net (code "60") (name "MOSI") (class "Default")
      (node (ref "IC1") (pin "80") (pinfunction "PC12_80") (pintype "bidirectional"))
      (node (ref "MPU-SIG") (pin "P$3") (pinfunction "3_P$3") (pintype "bidirectional"))
      (node (ref "SPI-R") (pin "P$3") (pinfunction "3_P$3") (pintype "bidirectional"))
    )
    (net (code "61") (name "MOTOR-CH1") (class "Default")
      (node (ref "IC1") (pin "40") (pinfunction "PE9_40") (pintype "bidirectional"))
      (node (ref "MOTOR1") (pin "P$1") (pinfunction "1_P$1") (pintype "bidirectional"))
    )
    (net (code "62") (name "MOTOR-CH2") (class "Default")
      (node (ref "IC1") (pin "42") (pinfunction "PE11_42") (pintype "bidirectional"))
      (node (ref "MOTOR2") (pin "P$1") (pinfunction "1_P$1") (pintype "bidirectional"))
    )
    (net (code "63") (name "MOTOR-CH3") (class "Default")
      (node (ref "IC1") (pin "44") (pinfunction "PE13_44") (pintype "bidirectional"))
      (node (ref "MOTOR3") (pin "P$1") (pinfunction "1_P$1") (pintype "bidirectional"))
    )
    (net (code "64") (name "MOTOR-CH4") (class "Default")
      (node (ref "IC1") (pin "45") (pinfunction "PE14_45") (pintype "bidirectional"))
      (node (ref "MOTOR4") (pin "P$1") (pinfunction "1_P$1") (pintype "bidirectional"))
    )
    (net (code "65") (name "MOTOR-FET") (class "Default")
      (node (ref "LIPO") (pin "3") (pinfunction "3_3") (pintype "passive"))
      (node (ref "TO-UI3") (pin "2") (pinfunction "2_2") (pintype "passive"))
    )
    (net (code "66") (name "MPU-SIG") (class "Default")
      (node (ref "IC1") (pin "81") (pinfunction "PD0_81") (pintype "bidirectional"))
      (node (ref "MPU-SIG") (pin "P$1") (pinfunction "1_P$1") (pintype "bidirectional"))
    )
    (net (code "67") (name "NRST") (class "Default")
      (node (ref "IC1") (pin "14") (pinfunction "NRST_14") (pintype "bidirectional"))
      (node (ref "RESET-STM") (pin "3") (pinfunction "3_3") (pintype "passive"))
      (node (ref "RESET-STM") (pin "4") (pinfunction "4_4") (pintype "passive"))
      (node (ref "ST-LINKV2") (pin "5") (pinfunction "5_5") (pintype "passive"))
      (node (ref "STM-R1") (pin "1") (pinfunction "1_1") (pintype "passive"))
      (node (ref "TO-UI3") (pin "9") (pinfunction "9_9") (pintype "passive"))
    )
    (net (code "68") (name "Net-(3.3REG-ON{slash}OFF)") (class "Default")
      (node (ref "3.3REG") (pin "1") (pinfunction "ON/OFF_1") (pintype "bidirectional"))
      (node (ref "SJ6") (pin "2") (pinfunction "2_2") (pintype "passive"))
      (node (ref "SP-R4") (pin "1") (pinfunction "1_1") (pintype "passive"))
    )
    (net (code "69") (name "Net-(3.3REG-TRIM)") (class "Default")
      (node (ref "3.3REG") (pin "6") (pinfunction "TRIM_6") (pintype "bidirectional"))
      (node (ref "SP-RC2") (pin "3") (pinfunction "E_3") (pintype "passive"))
    )
    (net (code "70") (name "Net-(5VREG-ON{slash}OFF)") (class "Default")
      (node (ref "5VREG") (pin "1") (pinfunction "ON/OFF_1") (pintype "bidirectional"))
      (node (ref "SJ5") (pin "2") (pinfunction "2_2") (pintype "passive"))
      (node (ref "SP-R2") (pin "1") (pinfunction "1_1") (pintype "passive"))
    )
    (net (code "71") (name "Net-(5VREG-TRIM)") (class "Default")
      (node (ref "5VREG") (pin "6") (pinfunction "TRIM_6") (pintype "bidirectional"))
      (node (ref "SP-RC1") (pin "3") (pinfunction "E_3") (pintype "passive"))
    )
    (net (code "72") (name "Net-(50MHZ-OUT)") (class "Default")
      (node (ref "50MHZ") (pin "3") (pinfunction "OUT_3") (pintype "output"))
      (node (ref "NT-JP") (pin "2") (pinfunction "2_2") (pintype "passive"))
    )
    (net (code "73") (name "Net-(100-Pad2)") (class "Default")
      (node (ref "100") (pin "2") (pinfunction "2_2") (pintype "passive"))
      (node (ref "SP-LED2") (pin "C") (pinfunction "C_C") (pintype "passive"))
    )
    (net (code "74") (name "Net-(BAT-JP1-Pad1)") (class "Default")
      (node (ref "BAT-JP1") (pin "1") (pinfunction "1_1") (pintype "passive"))
      (node (ref "BAT-R1") (pin "2") (pinfunction "2_2") (pintype "passive"))
      (node (ref "BAT-R2") (pin "1") (pinfunction "1_1") (pintype "passive"))
    )
    (net (code "75") (name "Net-(CAN-C1-Pad2)") (class "Default")
      (node (ref "CAN-C1") (pin "2") (pinfunction "2_2") (pintype "passive"))
      (node (ref "CAN-R1") (pin "1") (pinfunction "1_1") (pintype "passive"))
      (node (ref "CAN-R2") (pin "1") (pinfunction "1_1") (pintype "passive"))
    )
    (net (code "76") (name "Net-(CN1-LED1_K)") (class "Default")
      (node (ref "CN1") (pin "10") (pinfunction "LED1_K_10") (pintype "bidirectional"))
      (node (ref "NT-R10") (pin "2") (pinfunction "2_2") (pintype "passive"))
    )
    (net (code "77") (name "Net-(CN1-LED2_K)") (class "Default")
      (node (ref "CN1") (pin "11") (pinfunction "LED2_K_11") (pintype "bidirectional"))
      (node (ref "NT-R11") (pin "2") (pinfunction "2_2") (pintype "passive"))
    )
    (net (code "78") (name "Net-(FETR2A-2)") (class "Default")
      (node (ref "FET-R9") (pin "1") (pinfunction "1_1") (pintype "passive"))
      (node (ref "FETR2") (pin "8") (pinfunction "2_8") (pintype "passive"))
      (node (ref "T3") (pin "2") (pinfunction "G_2") (pintype "passive"))
    )
    (net (code "79") (name "Net-(FETR2B-2)") (class "Default")
      (node (ref "FET-R10") (pin "1") (pinfunction "1_1") (pintype "passive"))
      (node (ref "FETR2") (pin "7") (pinfunction "2_7") (pintype "passive"))
      (node (ref "T3") (pin "4") (pinfunction "G_4") (pintype "passive"))
    )
    (net (code "80") (name "Net-(FETR2C-2)") (class "Default")
      (node (ref "FET-R13") (pin "1") (pinfunction "1_1") (pintype "passive"))
      (node (ref "FETR2") (pin "6") (pinfunction "2_6") (pintype "passive"))
      (node (ref "T4") (pin "2") (pinfunction "G_2") (pintype "passive"))
    )
    (net (code "81") (name "Net-(FETR2D-2)") (class "Default")
      (node (ref "FET-R14") (pin "1") (pinfunction "1_1") (pintype "passive"))
      (node (ref "FETR2") (pin "5") (pinfunction "2_5") (pintype "passive"))
      (node (ref "T4") (pin "4") (pinfunction "G_4") (pintype "passive"))
    )
    (net (code "82") (name "Net-(IC1A-OSC_IN)") (class "Default")
      (node (ref "8MHZ") (pin "2") (pinfunction "2_2") (pintype "passive"))
      (node (ref "C5") (pin "2") (pinfunction "2_2") (pintype "passive"))
      (node (ref "IC1") (pin "12") (pinfunction "OSC_IN_12") (pintype "bidirectional"))
    )
    (net (code "83") (name "Net-(IC1A-OSC_OUT)") (class "Default")
      (node (ref "8MHZ") (pin "1") (pinfunction "1_1") (pintype "passive"))
      (node (ref "C6") (pin "2") (pinfunction "2_2") (pintype "passive"))
      (node (ref "IC1") (pin "13") (pinfunction "OSC_OUT_13") (pintype "bidirectional"))
    )
    (net (code "84") (name "Net-(IC1A-PA3)") (class "Default")
      (node (ref "BAT-JP1") (pin "2") (pinfunction "2_2") (pintype "passive"))
      (node (ref "IC1") (pin "26") (pinfunction "PA3_26") (pintype "bidirectional"))
    )
    (net (code "85") (name "Net-(IC1A-PD5)") (class "Default")
      (node (ref "IC1") (pin "86") (pinfunction "PD5_86") (pintype "bidirectional"))
      (node (ref "IC2") (pin "4") (pinfunction "DI_4") (pintype "input"))
    )
    (net (code "86") (name "Net-(IC1A-PD6)") (class "Default")
      (node (ref "IC1") (pin "87") (pinfunction "PD6_87") (pintype "bidirectional"))
      (node (ref "IC2") (pin "1") (pinfunction "RO_1") (pintype "output"))
    )
    (net (code "87") (name "Net-(IC1A-VCAP1)") (class "Default")
      (node (ref "IC1") (pin "49") (pinfunction "VCAP1_49") (pintype "power_in"))
      (node (ref "STM-C6") (pin "1") (pinfunction "1_1") (pintype "passive"))
    )
    (net (code "88") (name "Net-(IC1A-VCAP2)") (class "Default")
      (node (ref "IC1") (pin "73") (pinfunction "VCAP2_73") (pintype "power_in"))
      (node (ref "STM-C5") (pin "1") (pinfunction "1_1") (pintype "passive"))
    )
    (net (code "89") (name "Net-(IC3-ANA18VDD)") (class "Default")
      (node (ref "IC3") (pin "18") (pinfunction "ANA18VDD_18") (pintype "power_in"))
      (node (ref "NT-C3") (pin "2") (pinfunction "2_2") (pintype "passive"))
    )
    (net (code "90") (name "Net-(IC3-CORE_VDD)") (class "Default")
      (node (ref "IC3") (pin "37") (pinfunction "CORE_VDD_37") (pintype "power_in"))
      (node (ref "NT-C5") (pin "1") (pinfunction "1_1") (pintype "passive"))
    )
    (net (code "91") (name "Net-(IC3-IP_PH_M)") (class "Default")
      (node (ref "IC3") (pin "20") (pinfunction "IP_PH_M_20") (pintype "input"))
      (node (ref "NT-R5") (pin "1") (pinfunction "1_1") (pintype "passive"))
    )
    (net (code "92") (name "Net-(IC3-IP_PH_P)") (class "Default")
      (node (ref "IC3") (pin "21") (pinfunction "IP_PH_P_21") (pintype "input"))
      (node (ref "NT-R4") (pin "1") (pinfunction "1_1") (pintype "passive"))
    )
    (net (code "93") (name "Net-(IC3-REG_OUT)") (class "Default")
      (node (ref "IC3") (pin "23") (pinfunction "REG_OUT_23") (pintype "output"))
      (node (ref "NT-C2") (pin "2") (pinfunction "2_2") (pintype "passive"))
    )
    (net (code "94") (name "Net-(IC3-RESET_N)") (class "Default")
      (node (ref "IC3") (pin "29") (pinfunction "RESET_N_29") (pintype "input"))
      (node (ref "NT-RST-R") (pin "1") (pinfunction "1_1") (pintype "passive"))
      (node (ref "S5") (pin "1") (pinfunction "1_1") (pintype "bidirectional"))
      (node (ref "S5") (pin "2") (pinfunction "2_2") (pintype "bidirectional"))
    )
    (net (code "95") (name "Net-(IC3-RX_DV)") (class "Default")
      (node (ref "IC3") (pin "39") (pinfunction "RX_DV_39") (pintype "bidirectional"))
      (node (ref "NT-R2") (pin "1") (pinfunction "1_1") (pintype "passive"))
    )
    (net (code "96") (name "Net-(IC3-VREF)") (class "Default")
      (node (ref "IC3") (pin "24") (pinfunction "VREF_24") (pintype "bidirectional"))
      (node (ref "NT-C2") (pin "1") (pinfunction "1_1") (pintype "passive"))
      (node (ref "NT-R3") (pin "2") (pinfunction "2_2") (pintype "passive"))
    )
    (net (code "97") (name "Net-(LED1-Pad1)") (class "Default")
      (node (ref "LED1") (pin "1") (pinfunction "1_1") (pintype "passive"))
      (node (ref "SJ2") (pin "2") (pinfunction "2_2") (pintype "passive"))
    )
    (net (code "98") (name "Net-(LED2-Pad1)") (class "Default")
      (node (ref "LED2") (pin "1") (pinfunction "1_1") (pintype "passive"))
      (node (ref "SJ4") (pin "2") (pinfunction "2_2") (pintype "passive"))
    )
    (net (code "99") (name "Net-(LED3-Pad1)") (class "Default")
      (node (ref "LED3") (pin "1") (pinfunction "1_1") (pintype "passive"))
      (node (ref "SJ1") (pin "2") (pinfunction "2_2") (pintype "passive"))
    )
    (net (code "100") (name "Net-(LED4-Pad1)") (class "Default")
      (node (ref "LED4") (pin "1") (pinfunction "1_1") (pintype "passive"))
      (node (ref "SJ3") (pin "2") (pinfunction "2_2") (pintype "passive"))
    )
    (net (code "101") (name "Net-(MOTOR1-2)") (class "Default")
      (node (ref "M-JP-VCC") (pin "2") (pinfunction "2_2") (pintype "passive"))
      (node (ref "MOTOR1") (pin "P$2") (pinfunction "2_P$2") (pintype "bidirectional"))
      (node (ref "MOTOR2") (pin "P$2") (pinfunction "2_P$2") (pintype "bidirectional"))
      (node (ref "MOTOR3") (pin "P$2") (pinfunction "2_P$2") (pintype "bidirectional"))
      (node (ref "MOTOR4") (pin "P$2") (pinfunction "2_P$2") (pintype "bidirectional"))
    )
    (net (code "102") (name "Net-(MOTOR1-3)") (class "Default")
      (node (ref "M-JP-GND") (pin "1") (pinfunction "1_1") (pintype "passive"))
      (node (ref "MOTOR1") (pin "P$3") (pinfunction "3_P$3") (pintype "bidirectional"))
      (node (ref "MOTOR2") (pin "P$3") (pinfunction "3_P$3") (pintype "bidirectional"))
      (node (ref "MOTOR3") (pin "P$3") (pinfunction "3_P$3") (pintype "bidirectional"))
      (node (ref "MOTOR4") (pin "P$3") (pinfunction "3_P$3") (pintype "bidirectional"))
    )
    (net (code "103") (name "Net-(S2-P)") (class "Default")
      (node (ref "S2") (pin "2") (pinfunction "P_2") (pintype "passive"))
      (node (ref "VOLTAGE-METER2") (pin "P$1") (pinfunction "1_P$1") (pintype "bidirectional"))
    )
    (net (code "104") (name "Net-(SP-LED1-PadC)") (class "Default")
      (node (ref "SP-LED1") (pin "C") (pinfunction "C_C") (pintype "passive"))
      (node (ref "SP-R5") (pin "2") (pinfunction "2_2") (pintype "passive"))
    )
    (net (code "105") (name "Net-(SP-RC1-A)") (class "Default")
      (node (ref "SP-R1") (pin "2") (pinfunction "2_2") (pintype "passive"))
      (node (ref "SP-RC1") (pin "1") (pinfunction "A_1") (pintype "passive"))
      (node (ref "SP-RC1") (pin "2") (pinfunction "S_2") (pintype "passive"))
    )
    (net (code "106") (name "Net-(SP-RC2-A)") (class "Default")
      (node (ref "SP-R3") (pin "2") (pinfunction "2_2") (pintype "passive"))
      (node (ref "SP-RC2") (pin "1") (pinfunction "A_1") (pintype "passive"))
      (node (ref "SP-RC2") (pin "2") (pinfunction "S_2") (pintype "passive"))
    )
    (net (code "107") (name "Net-(U$2-VCC)") (class "Default")
      (node (ref "Q3") (pin "D") (pinfunction "D_D") (pintype "passive"))
      (node (ref "U$2") (pin "+") (pinfunction "VCC_+") (pintype "bidirectional"))
      (node (ref "X2") (pin "1") (pinfunction "1_1") (pintype "passive"))
    )
    (net (code "108") (name "Net-(USB-POLY-Pad2)") (class "Default")
      (node (ref "USB-POLY") (pin "2") (pinfunction "2_2") (pintype "passive"))
      (node (ref "X3") (pin "1") (pinfunction "1_1") (pintype "passive"))
    )
    (net (code "109") (name "Net-(XB1-~{RESET})") (class "Default")
      (node (ref "S4") (pin "3") (pinfunction "3_3") (pintype "bidirectional"))
      (node (ref "S4") (pin "4") (pinfunction "4_4") (pintype "bidirectional"))
      (node (ref "XB1") (pin "5") (pinfunction "~{RESET}_5") (pintype "input"))
      (node (ref "XBEE-RST") (pin "1") (pinfunction "1_1") (pintype "passive"))
    )
    (net (code "110") (name "PING") (class "Default")
      (node (ref "IC1") (pin "93") (pinfunction "PB7_93") (pintype "bidirectional"))
      (node (ref "PING") (pin "P$1") (pinfunction "1_P$1") (pintype "bidirectional"))
    )
    (net (code "111") (name "RD+") (class "Default")
      (node (ref "CN1") (pin "7") (pinfunction "RX+_7") (pintype "bidirectional"))
      (node (ref "IC3") (pin "14") (pinfunction "TPRDP_14") (pintype "bidirectional"))
      (node (ref "NT-R8") (pin "1") (pinfunction "1_1") (pintype "passive"))
    )
    (net (code "112") (name "RD-") (class "Default")
      (node (ref "CN1") (pin "8") (pinfunction "RX-_8") (pintype "bidirectional"))
      (node (ref "IC3") (pin "13") (pinfunction "TPRDM_13") (pintype "bidirectional"))
      (node (ref "NT-R9") (pin "2") (pinfunction "2_2") (pintype "passive"))
    )
    (net (code "113") (name "RO1-CHA") (class "Default")
      (node (ref "IC1") (pin "63") (pinfunction "PC6_63") (pintype "bidirectional"))
      (node (ref "RO-R") (pin "8") (pinfunction "2_8") (pintype "passive"))
      (node (ref "RO1") (pin "P$3") (pinfunction "3_P$3") (pintype "bidirectional"))
    )
    (net (code "114") (name "RO1-CHB") (class "Default")
      (node (ref "IC1") (pin "64") (pinfunction "PC7_64") (pintype "bidirectional"))
      (node (ref "RO-R") (pin "7") (pinfunction "2_7") (pintype "passive"))
      (node (ref "RO1") (pin "P$4") (pinfunction "4_P$4") (pintype "bidirectional"))
    )
    (net (code "115") (name "RO2-CHA") (class "Default")
      (node (ref "IC1") (pin "30") (pinfunction "PA5_30") (pintype "bidirectional"))
      (node (ref "RO-R") (pin "6") (pinfunction "2_6") (pintype "passive"))
      (node (ref "RO2") (pin "P$3") (pinfunction "3_P$3") (pintype "bidirectional"))
    )
    (net (code "116") (name "RO2-CHB") (class "Default")
      (node (ref "IC1") (pin "89") (pinfunction "PB3_89") (pintype "bidirectional"))
      (node (ref "RO-R") (pin "5") (pinfunction "2_5") (pintype "passive"))
      (node (ref "RO2") (pin "P$4") (pinfunction "4_P$4") (pintype "bidirectional"))
    )
    (net (code "117") (name "RPI-RX") (class "Default")
      (node (ref "IC1") (pin "97") (pinfunction "PE0_97") (pintype "bidirectional"))
      (node (ref "X1") (pin "8") (pinfunction "TXD_8") (pintype "bidirectional"))
    )
    (net (code "118") (name "RPI-TX") (class "Default")
      (node (ref "IC1") (pin "98") (pinfunction "PE1_98") (pintype "bidirectional"))
      (node (ref "X1") (pin "10") (pinfunction "RXD_10") (pintype "bidirectional"))
    )
    (net (code "119") (name "RS-CHA") (class "Default")
      (node (ref "IC2") (pin "6") (pinfunction "A_6") (pintype "bidirectional"))
      (node (ref "RS485-S") (pin "1") (pinfunction "1_1") (pintype "passive"))
      (node (ref "TO-F7") (pin "6") (pinfunction "6_6") (pintype "passive"))
    )
    (net (code "120") (name "RS-CHB") (class "Default")
      (node (ref "IC2") (pin "7") (pinfunction "B_7") (pintype "bidirectional"))
      (node (ref "RS485-S") (pin "2") (pinfunction "2_2") (pintype "passive"))
      (node (ref "TO-F7") (pin "5") (pinfunction "5_5") (pintype "passive"))
    )
    (net (code "121") (name "RS-SIG1") (class "Default")
      (node (ref "IC1") (pin "96") (pinfunction "PB9_96") (pintype "bidirectional"))
      (node (ref "X1") (pin "38") (pinfunction "GPIO20_38") (pintype "bidirectional"))
    )
    (net (code "122") (name "RS-SIG2") (class "Default")
      (node (ref "IC1") (pin "95") (pinfunction "PB8_95") (pintype "bidirectional"))
      (node (ref "X1") (pin "40") (pinfunction "GPIO21_40") (pintype "bidirectional"))
    )
    (net (code "123") (name "SCK") (class "Default")
      (node (ref "IC1") (pin "78") (pinfunction "PC10_78") (pintype "bidirectional"))
      (node (ref "MPU-SIG") (pin "P$5") (pinfunction "5_P$5") (pintype "bidirectional"))
      (node (ref "SPI-R") (pin "P$5") (pinfunction "5_P$5") (pintype "bidirectional"))
    )
    (net (code "124") (name "SCL") (class "Default")
      (node (ref "I2C-R") (pin "P$2") (pinfunction "2_P$2") (pintype "bidirectional"))
      (node (ref "I2C-R1") (pin "2") (pinfunction "2_2") (pintype "passive"))
      (node (ref "IC1") (pin "67") (pinfunction "PA8_67") (pintype "bidirectional"))
      (node (ref "JY901") (pin "P$2") (pinfunction "2_P$2") (pintype "bidirectional"))
    )
    (net (code "125") (name "SDA") (class "Default")
      (node (ref "I2C-R") (pin "P$3") (pinfunction "3_P$3") (pintype "bidirectional"))
      (node (ref "I2C-R2") (pin "2") (pinfunction "2_2") (pintype "passive"))
      (node (ref "IC1") (pin "66") (pinfunction "PC9_66") (pintype "bidirectional"))
      (node (ref "JY901") (pin "P$3") (pinfunction "3_P$3") (pintype "bidirectional"))
    )
    (net (code "126") (name "SPI-R-SS") (class "Default")
      (node (ref "IC1") (pin "82") (pinfunction "PD1_82") (pintype "bidirectional"))
      (node (ref "SPI-R") (pin "P$1") (pinfunction "1_P$1") (pintype "bidirectional"))
    )
    (net (code "127") (name "SWCLK") (class "Default")
      (node (ref "IC1") (pin "76") (pinfunction "PA14_76") (pintype "bidirectional"))
      (node (ref "ST-LINKV2") (pin "2") (pinfunction "2_2") (pintype "passive"))
      (node (ref "TO-UI3") (pin "10") (pinfunction "10_10") (pintype "passive"))
    )
    (net (code "128") (name "SWDIO") (class "Default")
      (node (ref "IC1") (pin "72") (pinfunction "PA13_72") (pintype "bidirectional"))
      (node (ref "ST-LINKV2") (pin "4") (pinfunction "4_4") (pintype "passive"))
      (node (ref "TO-UI3") (pin "11") (pinfunction "11_11") (pintype "passive"))
    )
    (net (code "129") (name "TD+") (class "Default")
      (node (ref "CN1") (pin "1") (pinfunction "TX+_1") (pintype "bidirectional"))
      (node (ref "IC3") (pin "17") (pinfunction "TPTDP_17") (pintype "bidirectional"))
      (node (ref "NT-R6") (pin "2") (pinfunction "2_2") (pintype "passive"))
    )
    (net (code "130") (name "TD-") (class "Default")
      (node (ref "CN1") (pin "2") (pinfunction "TX-_2") (pintype "bidirectional"))
      (node (ref "IC3") (pin "16") (pinfunction "TPTDM_16") (pintype "bidirectional"))
      (node (ref "NT-R7") (pin "1") (pinfunction "1_1") (pintype "passive"))
    )
    (net (code "131") (name "USB-D+") (class "Default")
      (node (ref "IC1") (pin "54") (pinfunction "PB15_54") (pintype "bidirectional"))
      (node (ref "X3") (pin "3") (pinfunction "3_3") (pintype "passive"))
    )
    (net (code "132") (name "USB-D-") (class "Default")
      (node (ref "IC1") (pin "53") (pinfunction "PB14_53") (pintype "bidirectional"))
      (node (ref "X3") (pin "2") (pinfunction "2_2") (pintype "passive"))
    )
    (net (code "133") (name "unconnected-(3.3REG-NC_1-Pad8)") (class "Default")
      (node (ref "3.3REG") (pin "8") (pinfunction "NC_1_8") (pintype "bidirectional"))
    )
    (net (code "134") (name "unconnected-(3.3REG-NC_2-Pad11)") (class "Default")
      (node (ref "3.3REG") (pin "11") (pinfunction "NC_2_11") (pintype "bidirectional"))
    )
    (net (code "135") (name "unconnected-(3.3REG-NC_3-Pad12)") (class "Default")
      (node (ref "3.3REG") (pin "12") (pinfunction "NC_3_12") (pintype "bidirectional"))
    )
    (net (code "136") (name "unconnected-(3.3REG-PGOOD-Pad10)") (class "Default")
      (node (ref "3.3REG") (pin "10") (pinfunction "PGOOD_10") (pintype "bidirectional"))
    )
    (net (code "137") (name "unconnected-(3.3REG-SEQ-Pad9)") (class "Default")
      (node (ref "3.3REG") (pin "9") (pinfunction "SEQ_9") (pintype "bidirectional"))
    )
    (net (code "138") (name "unconnected-(5VREG-NC_1-Pad8)") (class "Default")
      (node (ref "5VREG") (pin "8") (pinfunction "NC_1_8") (pintype "bidirectional"))
    )
    (net (code "139") (name "unconnected-(5VREG-NC_2-Pad11)") (class "Default")
      (node (ref "5VREG") (pin "11") (pinfunction "NC_2_11") (pintype "bidirectional"))
    )
    (net (code "140") (name "unconnected-(5VREG-NC_3-Pad12)") (class "Default")
      (node (ref "5VREG") (pin "12") (pinfunction "NC_3_12") (pintype "bidirectional"))
    )
    (net (code "141") (name "unconnected-(5VREG-PGOOD-Pad10)") (class "Default")
      (node (ref "5VREG") (pin "10") (pinfunction "PGOOD_10") (pintype "bidirectional"))
    )
    (net (code "142") (name "unconnected-(5VREG-SEQ-Pad9)") (class "Default")
      (node (ref "5VREG") (pin "9") (pinfunction "SEQ_9") (pintype "bidirectional"))
    )
    (net (code "143") (name "unconnected-(50MHZ-TRI-Pad1)") (class "Default")
      (node (ref "50MHZ") (pin "1") (pinfunction "TRI_1") (pintype "input"))
    )
    (net (code "144") (name "unconnected-(IC1A-PA0-Pad23)") (class "Default")
      (node (ref "IC1") (pin "23") (pinfunction "PA0_23") (pintype "bidirectional"))
    )
    (net (code "145") (name "unconnected-(IC1A-PA4-Pad29)") (class "Default")
      (node (ref "IC1") (pin "29") (pinfunction "PA4_29") (pintype "bidirectional"))
    )
    (net (code "146") (name "unconnected-(IC1A-PA6-Pad31)") (class "Default")
      (node (ref "IC1") (pin "31") (pinfunction "PA6_31") (pintype "bidirectional"))
    )
    (net (code "147") (name "unconnected-(IC1A-PA11-Pad70)") (class "Default")
      (node (ref "IC1") (pin "70") (pinfunction "PA11_70") (pintype "bidirectional"))
    )
    (net (code "148") (name "unconnected-(IC1A-PA12-Pad71)") (class "Default")
      (node (ref "IC1") (pin "71") (pinfunction "PA12_71") (pintype "bidirectional"))
    )
    (net (code "149") (name "unconnected-(IC1A-PA15-Pad77)") (class "Default")
      (node (ref "IC1") (pin "77") (pinfunction "PA15_77") (pintype "bidirectional"))
    )
    (net (code "150") (name "unconnected-(IC1A-PB2-Pad37)") (class "Default")
      (node (ref "IC1") (pin "37") (pinfunction "PB2_37") (pintype "bidirectional"))
    )
    (net (code "151") (name "unconnected-(IC1A-PB4-Pad90)") (class "Default")
      (node (ref "IC1") (pin "90") (pinfunction "PB4_90") (pintype "bidirectional"))
    )
    (net (code "152") (name "unconnected-(IC1A-PB10-Pad47)") (class "Default")
      (node (ref "IC1") (pin "47") (pinfunction "PB10_47") (pintype "bidirectional"))
    )
    (net (code "153") (name "unconnected-(IC1A-PC8-Pad65)") (class "Default")
      (node (ref "IC1") (pin "65") (pinfunction "PC8_65") (pintype "bidirectional"))
    )
    (net (code "154") (name "unconnected-(IC1A-PD7-Pad88)") (class "Default")
      (node (ref "IC1") (pin "88") (pinfunction "PD7_88") (pintype "bidirectional"))
    )
    (net (code "155") (name "unconnected-(IC1A-PD14-Pad61)") (class "Default")
      (node (ref "IC1") (pin "61") (pinfunction "PD14_61") (pintype "bidirectional"))
    )
    (net (code "156") (name "unconnected-(IC1A-PD15-Pad62)") (class "Default")
      (node (ref "IC1") (pin "62") (pinfunction "PD15_62") (pintype "bidirectional"))
    )
    (net (code "157") (name "unconnected-(IC1A-PE7-Pad38)") (class "Default")
      (node (ref "IC1") (pin "38") (pinfunction "PE7_38") (pintype "bidirectional"))
    )
    (net (code "158") (name "unconnected-(IC1A-PE8-Pad39)") (class "Default")
      (node (ref "IC1") (pin "39") (pinfunction "PE8_39") (pintype "bidirectional"))
    )
    (net (code "159") (name "unconnected-(IC1A-PE10-Pad41)") (class "Default")
      (node (ref "IC1") (pin "41") (pinfunction "PE10_41") (pintype "bidirectional"))
    )
    (net (code "160") (name "unconnected-(IC1A-PE12-Pad43)") (class "Default")
      (node (ref "IC1") (pin "43") (pinfunction "PE12_43") (pintype "bidirectional"))
    )
    (net (code "161") (name "unconnected-(IC1A-PE15-Pad46)") (class "Default")
      (node (ref "IC1") (pin "46") (pinfunction "PE15_46") (pintype "bidirectional"))
    )
    (net (code "162") (name "unconnected-(IC3-CLK2MAC-Pad25)") (class "Default")
      (node (ref "IC3") (pin "25") (pinfunction "CLK2MAC_25") (pintype "bidirectional"))
    )
    (net (code "163") (name "unconnected-(IC3-COL-Pad42)") (class "Default")
      (node (ref "IC3") (pin "42") (pinfunction "COL_42") (pintype "bidirectional"))
    )
    (net (code "164") (name "unconnected-(IC3-LED_SPD-Pad27)") (class "Default")
      (node (ref "IC3") (pin "27") (pinfunction "LED_SPD_27") (pintype "bidirectional"))
    )
    (net (code "165") (name "unconnected-(IC3-PWRDN_INTN-Pad7)") (class "Default")
      (node (ref "IC3") (pin "7") (pinfunction "PWRDN_INTN_7") (pintype "bidirectional"))
    )
    (net (code "166") (name "unconnected-(IC3-RXD_2-Pad45)") (class "Default")
      (node (ref "IC3") (pin "45") (pinfunction "RXD_2_45") (pintype "bidirectional"))
    )
    (net (code "167") (name "unconnected-(IC3-RXD_3-Pad46)") (class "Default")
      (node (ref "IC3") (pin "46") (pinfunction "RXD_3_46") (pintype "bidirectional"))
    )
    (net (code "168") (name "unconnected-(IC3-RX_CLK-Pad38)") (class "Default")
      (node (ref "IC3") (pin "38") (pinfunction "RX_CLK_38") (pintype "bidirectional"))
    )
    (net (code "169") (name "unconnected-(IC3-RX_ER-Pad41)") (class "Default")
      (node (ref "IC3") (pin "41") (pinfunction "RX_ER_41") (pintype "bidirectional"))
    )
    (net (code "170") (name "unconnected-(IC3-TCK-Pad8)") (class "Default")
      (node (ref "IC3") (pin "8") (pinfunction "TCK_8") (pintype "input"))
    )
    (net (code "171") (name "unconnected-(IC3-TDI-Pad12)") (class "Default")
      (node (ref "IC3") (pin "12") (pinfunction "TDI_12") (pintype "input"))
    )
    (net (code "172") (name "unconnected-(IC3-TDO-Pad9)") (class "Default")
      (node (ref "IC3") (pin "9") (pinfunction "TDO_9") (pintype "output"))
    )
    (net (code "173") (name "unconnected-(IC3-TMS-Pad10)") (class "Default")
      (node (ref "IC3") (pin "10") (pinfunction "TMS_10") (pintype "input"))
    )
    (net (code "174") (name "unconnected-(IC3-TRST_N-Pad11)") (class "Default")
      (node (ref "IC3") (pin "11") (pinfunction "TRST_N_11") (pintype "input"))
    )
    (net (code "175") (name "unconnected-(IC3-TXD_2-Pad5)") (class "Default")
      (node (ref "IC3") (pin "5") (pinfunction "TXD_2_5") (pintype "bidirectional"))
    )
    (net (code "176") (name "unconnected-(IC3-TXD_3-Pad6)") (class "Default")
      (node (ref "IC3") (pin "6") (pinfunction "TXD_3_6") (pintype "bidirectional"))
    )
    (net (code "177") (name "unconnected-(IC3-TX_CLK-Pad1)") (class "Default")
      (node (ref "IC3") (pin "1") (pinfunction "TX_CLK_1") (pintype "bidirectional"))
    )
    (net (code "178") (name "unconnected-(IC3-X2-Pad33)") (class "Default")
      (node (ref "IC3") (pin "33") (pinfunction "X2_33") (pintype "output"))
    )
    (net (code "179") (name "unconnected-(IC4-SPLIT-Pad5)") (class "Default")
      (node (ref "IC4") (pin "5") (pinfunction "SPLIT_5") (pintype "bidirectional"))
    )
    (net (code "180") (name "unconnected-(MAINSW2-Pad3)") (class "Default")
      (node (ref "MAINSW2") (pin "3") (pinfunction "3_3") (pintype "passive"))
    )
    (net (code "181") (name "unconnected-(S1-S-Pad3)") (class "Default")
      (node (ref "S1") (pin "3") (pinfunction "S_3") (pintype "passive"))
    )
    (net (code "182") (name "unconnected-(S3-S-Pad3)") (class "Default")
      (node (ref "S3") (pin "3") (pinfunction "S_3") (pintype "passive"))
    )
    (net (code "183") (name "unconnected-(ST-LINKV2-Pad6)") (class "Default")
      (node (ref "ST-LINKV2") (pin "6") (pinfunction "6_6") (pintype "passive"))
    )
    (net (code "184") (name "unconnected-(SUOPPLY-SW2-3-PadP$3)") (class "Default")
      (node (ref "SUOPPLY-SW2") (pin "P$3") (pinfunction "3_P$3") (pintype "bidirectional"))
    )
    (net (code "185") (name "unconnected-(TO-F7-Pad1)") (class "Default")
      (node (ref "TO-F7") (pin "1") (pinfunction "1_1") (pintype "passive"))
    )
    (net (code "186") (name "unconnected-(X1-GPIO04-Pad7)") (class "Default")
      (node (ref "X1") (pin "7") (pinfunction "GPIO04_7") (pintype "bidirectional"))
    )
    (net (code "187") (name "unconnected-(X1-GPIO06-Pad31)") (class "Default")
      (node (ref "X1") (pin "31") (pinfunction "GPIO06_31") (pintype "bidirectional"))
    )
    (net (code "188") (name "unconnected-(X1-GPIO12-Pad32)") (class "Default")
      (node (ref "X1") (pin "32") (pinfunction "GPIO12_32") (pintype "bidirectional"))
    )
    (net (code "189") (name "unconnected-(X1-GPIO13-Pad33)") (class "Default")
      (node (ref "X1") (pin "33") (pinfunction "GPIO13_33") (pintype "bidirectional"))
    )
    (net (code "190") (name "unconnected-(X1-GPIO16-Pad36)") (class "Default")
      (node (ref "X1") (pin "36") (pinfunction "GPIO16_36") (pintype "bidirectional"))
    )
    (net (code "191") (name "unconnected-(X1-GPIO18-Pad12)") (class "Default")
      (node (ref "X1") (pin "12") (pinfunction "GPIO18_12") (pintype "bidirectional"))
    )
    (net (code "192") (name "unconnected-(X1-GPIO19-Pad35)") (class "Default")
      (node (ref "X1") (pin "35") (pinfunction "GPIO19_35") (pintype "bidirectional"))
    )
    (net (code "193") (name "unconnected-(X1-GPIO22-Pad15)") (class "Default")
      (node (ref "X1") (pin "15") (pinfunction "GPIO22_15") (pintype "bidirectional"))
    )
    (net (code "194") (name "unconnected-(X1-GPIO23-Pad16)") (class "Default")
      (node (ref "X1") (pin "16") (pinfunction "GPIO23_16") (pintype "bidirectional"))
    )
    (net (code "195") (name "unconnected-(X1-GPIO24-Pad18)") (class "Default")
      (node (ref "X1") (pin "18") (pinfunction "GPIO24_18") (pintype "bidirectional"))
    )
    (net (code "196") (name "unconnected-(X1-GPIO25-Pad22)") (class "Default")
      (node (ref "X1") (pin "22") (pinfunction "GPIO25_22") (pintype "bidirectional"))
    )
    (net (code "197") (name "unconnected-(X1-GPIO26-Pad37)") (class "Default")
      (node (ref "X1") (pin "37") (pinfunction "GPIO26_37") (pintype "bidirectional"))
    )
    (net (code "198") (name "unconnected-(X1-ID_SC-Pad28)") (class "Default")
      (node (ref "X1") (pin "28") (pinfunction "ID_SC_28") (pintype "bidirectional"))
    )
    (net (code "199") (name "unconnected-(X1-ID_SD-Pad27)") (class "Default")
      (node (ref "X1") (pin "27") (pinfunction "ID_SD_27") (pintype "bidirectional"))
    )
    (net (code "200") (name "unconnected-(X1-SCL-Pad5)") (class "Default")
      (node (ref "X1") (pin "5") (pinfunction "SCL_5") (pintype "bidirectional"))
    )
    (net (code "201") (name "unconnected-(X1-SDA-Pad3)") (class "Default")
      (node (ref "X1") (pin "3") (pinfunction "SDA_3") (pintype "bidirectional"))
    )
    (net (code "202") (name "unconnected-(X1-SPI_CE0-Pad24)") (class "Default")
      (node (ref "X1") (pin "24") (pinfunction "SPI_CE0_24") (pintype "bidirectional"))
    )
    (net (code "203") (name "unconnected-(X1-SPI_CE1-Pad26)") (class "Default")
      (node (ref "X1") (pin "26") (pinfunction "SPI_CE1_26") (pintype "bidirectional"))
    )
    (net (code "204") (name "unconnected-(X1-SPI_MISO-Pad21)") (class "Default")
      (node (ref "X1") (pin "21") (pinfunction "SPI_MISO_21") (pintype "bidirectional"))
    )
    (net (code "205") (name "unconnected-(X1-SPI_MOSI-Pad19)") (class "Default")
      (node (ref "X1") (pin "19") (pinfunction "SPI_MOSI_19") (pintype "bidirectional"))
    )
    (net (code "206") (name "unconnected-(X1-SPI_SCLK-Pad23)") (class "Default")
      (node (ref "X1") (pin "23") (pinfunction "SPI_SCLK_23") (pintype "bidirectional"))
    )
    (net (code "207") (name "unconnected-(X2-Pad3)") (class "Default")
      (node (ref "X2") (pin "3") (pinfunction "3_3") (pintype "passive"))
    )
    (net (code "208") (name "unconnected-(XB1-AD0{slash}DIO0-Pad20)") (class "Default")
      (node (ref "XB1") (pin "20") (pinfunction "AD0/DIO0_20") (pintype "bidirectional"))
    )
    (net (code "209") (name "unconnected-(XB1-AD1{slash}DIO1-Pad19)") (class "Default")
      (node (ref "XB1") (pin "19") (pinfunction "AD1/DIO1_19") (pintype "bidirectional"))
    )
    (net (code "210") (name "unconnected-(XB1-AD2{slash}DIO2-Pad18)") (class "Default")
      (node (ref "XB1") (pin "18") (pinfunction "AD2/DIO2_18") (pintype "bidirectional"))
    )
    (net (code "211") (name "unconnected-(XB1-ASSOC{slash}AD5{slash}DIO5-Pad15)") (class "Default")
      (node (ref "XB1") (pin "15") (pinfunction "ASSOC/AD5/DIO5_15") (pintype "bidirectional"))
    )
    (net (code "212") (name "unconnected-(XB1-CD{slash}DOUT_EN{slash}DO8-Pad4)") (class "Default")
      (node (ref "XB1") (pin "4") (pinfunction "CD/DOUT_EN/DO8_4") (pintype "output"))
    )
    (net (code "213") (name "unconnected-(XB1-COORD_SEL{slash}AD3{slash}DIO3-Pad17)") (class "Default")
      (node (ref "XB1") (pin "17") (pinfunction "COORD_SEL/AD3/DIO3_17") (pintype "bidirectional"))
    )
    (net (code "214") (name "unconnected-(XB1-ON{slash}~{SLEEP}-Pad13)") (class "Default")
      (node (ref "XB1") (pin "13") (pinfunction "ON/~{SLEEP}_13") (pintype "output"))
    )
    (net (code "215") (name "unconnected-(XB1-PWM0{slash}RSSI-Pad6)") (class "Default")
      (node (ref "XB1") (pin "6") (pinfunction "PWM0/RSSI_6") (pintype "output"))
    )
    (net (code "216") (name "unconnected-(XB1-RF_TX{slash}AD4{slash}DIO4-Pad11)") (class "Default")
      (node (ref "XB1") (pin "11") (pinfunction "RF_TX/AD4/DIO4_11") (pintype "bidirectional"))
    )
    (net (code "217") (name "unconnected-(XB1-~{CTS}{slash}DIO7-Pad12)") (class "Default")
      (node (ref "XB1") (pin "12") (pinfunction "~{CTS}/DIO7_12") (pintype "bidirectional"))
    )
    (net (code "218") (name "unconnected-(XB1-~{DTR}{slash}SLEEP_RQ{slash}DI8-Pad9)") (class "Default")
      (node (ref "XB1") (pin "9") (pinfunction "~{DTR}/SLEEP_RQ/DI8_9") (pintype "bidirectional"))
    )
    (net (code "219") (name "unconnected-(XB1-~{RTS}{slash}AD6{slash}DIO6-Pad16)") (class "Default")
      (node (ref "XB1") (pin "16") (pinfunction "~{RTS}/AD6/DIO6_16") (pintype "bidirectional"))
    )
  )
)
